# Page_4_Power_CPU_DDR.net
KiCad netlist of a schematic drawn in Altium Designer
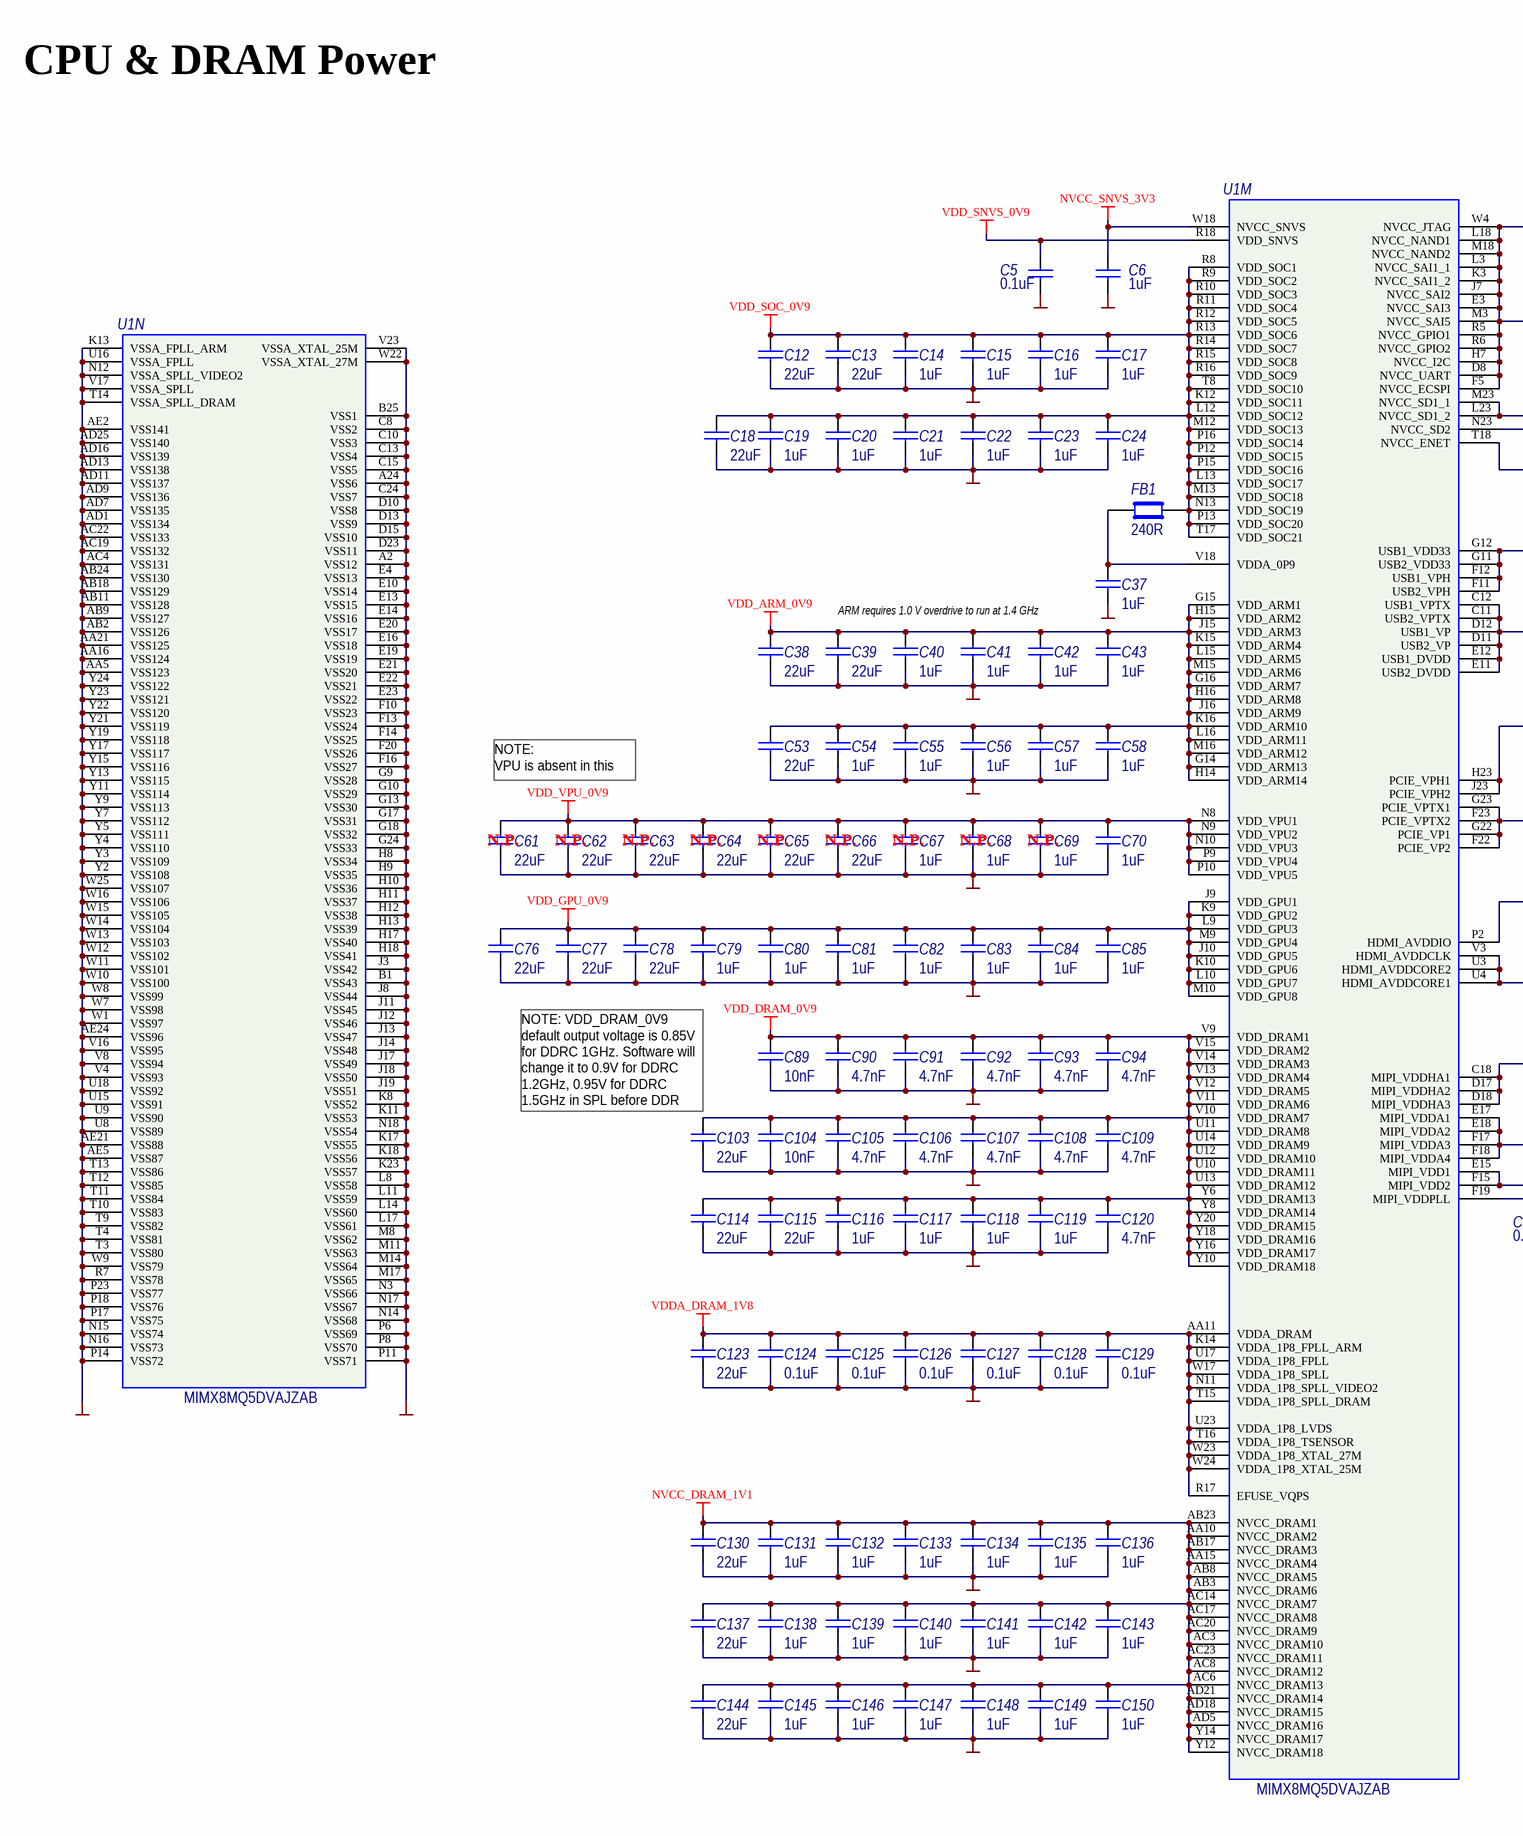
[diagram p0: Page 4_Power CPU_DDR.SchDoc, left]
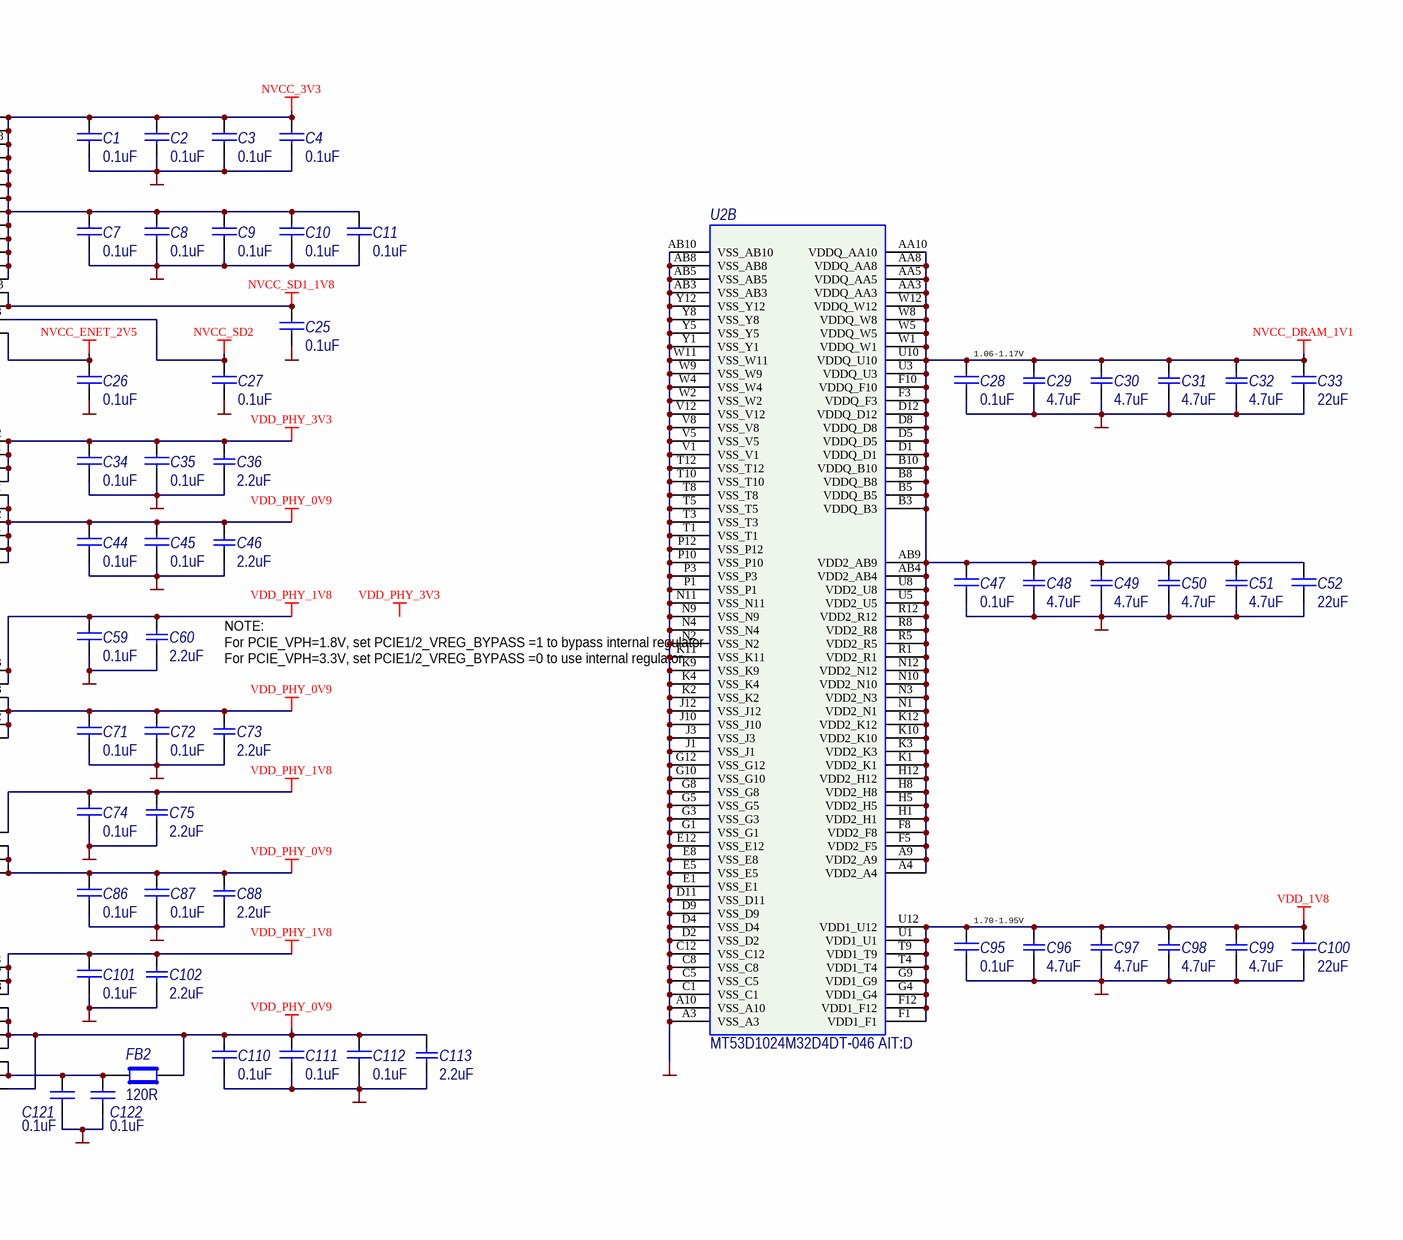
[diagram p1: Page 4_Power CPU_DDR.SchDoc, right]

(export (version "E")
  (design (tool "Eeschema 10.0.6"))
  (components
    (comp (ref "C1")
      (value "0.1uF")
      (footprint "CC0201_L-R")
      (description "CAP CER 0.1 uF 16V 10% X7R 0201")
      (fields
        (field (name "MANUFACTURER") "Murata")
        (field (name "MANUFACTURER PART NUMBER") "GRM033Z71C104KE14D")
      )
      (libsource (lib "CC0201") (part "GRM033Z71C104KE14D"))
    )
    (comp (ref "C2")
      (value "0.1uF")
      (footprint "CC0201_L-R")
      (description "CAP CER 0.1 uF 16V 10% X7R 0201")
      (fields
        (field (name "MANUFACTURER") "Murata")
        (field (name "MANUFACTURER PART NUMBER") "GRM033Z71C104KE14D")
      )
      (libsource (lib "CC0201") (part "GRM033Z71C104KE14D"))
    )
    (comp (ref "C3")
      (value "0.1uF")
      (footprint "CC0201_L-R")
      (description "CAP CER 0.1 uF 16V 10% X7R 0201")
      (fields
        (field (name "MANUFACTURER") "Murata")
        (field (name "MANUFACTURER PART NUMBER") "GRM033Z71C104KE14D")
      )
      (libsource (lib "CC0201") (part "GRM033Z71C104KE14D"))
    )
    (comp (ref "C4")
      (value "0.1uF")
      (footprint "CC0201_L-R")
      (description "CAP CER 0.1 uF 16V 10% X7R 0201")
      (fields
        (field (name "MANUFACTURER") "Murata")
        (field (name "MANUFACTURER PART NUMBER") "GRM033Z71C104KE14D")
      )
      (libsource (lib "CC0201") (part "GRM033Z71C104KE14D"))
    )
    (comp (ref "C5")
      (value "0.1uF")
      (footprint "CC0201_L-R")
      (description "CAP CER 0.1 uF 16V 10% X7R 0201")
      (fields
        (field (name "MANUFACTURER") "Murata")
        (field (name "MANUFACTURER PART NUMBER") "GRM033Z71C104KE14D")
      )
      (libsource (lib "CC0201") (part "GRM033Z71C104KE14D"))
    )
    (comp (ref "C6")
      (value "1uF")
      (footprint "CC0201_L-R")
      (description "CAP CER 1.0 uF 6.3V 10% X5R 0201")
      (fields
        (field (name "MANUFACTURER") "Yageo")
        (field (name "MANUFACTURER PART NUMBER") "CC0201KRX5R5BB105")
      )
      (libsource (lib "CC0201") (part "CC0201KRX5R5BB105"))
    )
    (comp (ref "C7")
      (value "0.1uF")
      (footprint "CC0201_L-R")
      (description "CAP CER 0.1 uF 16V 10% X7R 0201")
      (fields
        (field (name "MANUFACTURER") "Murata")
        (field (name "MANUFACTURER PART NUMBER") "GRM033Z71C104KE14D")
      )
      (libsource (lib "CC0201") (part "GRM033Z71C104KE14D"))
    )
    (comp (ref "C8")
      (value "0.1uF")
      (footprint "CC0201_L-R")
      (description "CAP CER 0.1 uF 16V 10% X7R 0201")
      (fields
        (field (name "MANUFACTURER") "Murata")
        (field (name "MANUFACTURER PART NUMBER") "GRM033Z71C104KE14D")
      )
      (libsource (lib "CC0201") (part "GRM033Z71C104KE14D"))
    )
    (comp (ref "C9")
      (value "0.1uF")
      (footprint "CC0201_L-R")
      (description "CAP CER 0.1 uF 16V 10% X7R 0201")
      (fields
        (field (name "MANUFACTURER") "Murata")
        (field (name "MANUFACTURER PART NUMBER") "GRM033Z71C104KE14D")
      )
      (libsource (lib "CC0201") (part "GRM033Z71C104KE14D"))
    )
    (comp (ref "C10")
      (value "0.1uF")
      (footprint "CC0201_L-R")
      (description "CAP CER 0.1 uF 16V 10% X7R 0201")
      (fields
        (field (name "MANUFACTURER") "Murata")
        (field (name "MANUFACTURER PART NUMBER") "GRM033Z71C104KE14D")
      )
      (libsource (lib "CC0201") (part "GRM033Z71C104KE14D"))
    )
    (comp (ref "C11")
      (value "0.1uF")
      (footprint "CC0201_L-R")
      (description "CAP CER 0.1 uF 16V 10% X7R 0201")
      (fields
        (field (name "MANUFACTURER") "Murata")
        (field (name "MANUFACTURER PART NUMBER") "GRM033Z71C104KE14D")
      )
      (libsource (lib "CC0201") (part "GRM033Z71C104KE14D"))
    )
    (comp (ref "C12")
      (value "22uF")
      (footprint "CC0603_H0.8_L-R")
      (description "CAP CER 22 uF 10V 20% X5R 0603")
      (fields
        (field (name "MANUFACTURER") "Murata")
        (field (name "MANUFACTURER PART NUMBER") "GRM188R61A226ME15J")
      )
      (libsource (lib "CC0603") (part "GRM188R61A226ME15J"))
    )
    (comp (ref "C13")
      (value "22uF")
      (footprint "CC0603_H0.8_L-R")
      (description "CAP CER 22 uF 10V 20% X5R 0603")
      (fields
        (field (name "MANUFACTURER") "Murata")
        (field (name "MANUFACTURER PART NUMBER") "GRM188R61A226ME15J")
      )
      (libsource (lib "CC0603") (part "GRM188R61A226ME15J"))
    )
    (comp (ref "C14")
      (value "1uF")
      (footprint "CC0201_L-R")
      (description "CAP CER 1.0 uF 6.3V 10% X5R 0201")
      (fields
        (field (name "MANUFACTURER") "Yageo")
        (field (name "MANUFACTURER PART NUMBER") "CC0201KRX5R5BB105")
      )
      (libsource (lib "CC0201") (part "CC0201KRX5R5BB105"))
    )
    (comp (ref "C15")
      (value "1uF")
      (footprint "CC0201_L-R")
      (description "CAP CER 1.0 uF 6.3V 10% X5R 0201")
      (fields
        (field (name "MANUFACTURER") "Yageo")
        (field (name "MANUFACTURER PART NUMBER") "CC0201KRX5R5BB105")
      )
      (libsource (lib "CC0201") (part "CC0201KRX5R5BB105"))
    )
    (comp (ref "C16")
      (value "1uF")
      (footprint "CC0201_L-R")
      (description "CAP CER 1.0 uF 6.3V 10% X5R 0201")
      (fields
        (field (name "MANUFACTURER") "Yageo")
        (field (name "MANUFACTURER PART NUMBER") "CC0201KRX5R5BB105")
      )
      (libsource (lib "CC0201") (part "CC0201KRX5R5BB105"))
    )
    (comp (ref "C17")
      (value "1uF")
      (footprint "CC0201_L-R")
      (description "CAP CER 1.0 uF 6.3V 10% X5R 0201")
      (fields
        (field (name "MANUFACTURER") "Yageo")
        (field (name "MANUFACTURER PART NUMBER") "CC0201KRX5R5BB105")
      )
      (libsource (lib "CC0201") (part "CC0201KRX5R5BB105"))
    )
    (comp (ref "C18")
      (value "22uF")
      (footprint "CC0603_H0.8_L-R")
      (description "CAP CER 22 uF 10V 20% X5R 0603")
      (fields
        (field (name "MANUFACTURER") "Murata")
        (field (name "MANUFACTURER PART NUMBER") "GRM188R61A226ME15J")
      )
      (libsource (lib "CC0603") (part "GRM188R61A226ME15J"))
    )
    (comp (ref "C19")
      (value "1uF")
      (footprint "CC0201_L-R")
      (description "CAP CER 1.0 uF 6.3V 10% X5R 0201")
      (fields
        (field (name "MANUFACTURER") "Yageo")
        (field (name "MANUFACTURER PART NUMBER") "CC0201KRX5R5BB105")
      )
      (libsource (lib "CC0201") (part "CC0201KRX5R5BB105"))
    )
    (comp (ref "C20")
      (value "1uF")
      (footprint "CC0201_L-R")
      (description "CAP CER 1.0 uF 6.3V 10% X5R 0201")
      (fields
        (field (name "MANUFACTURER") "Yageo")
        (field (name "MANUFACTURER PART NUMBER") "CC0201KRX5R5BB105")
      )
      (libsource (lib "CC0201") (part "CC0201KRX5R5BB105"))
    )
    (comp (ref "C21")
      (value "1uF")
      (footprint "CC0201_L-R")
      (description "CAP CER 1.0 uF 6.3V 10% X5R 0201")
      (fields
        (field (name "MANUFACTURER") "Yageo")
        (field (name "MANUFACTURER PART NUMBER") "CC0201KRX5R5BB105")
      )
      (libsource (lib "CC0201") (part "CC0201KRX5R5BB105"))
    )
    (comp (ref "C22")
      (value "1uF")
      (footprint "CC0201_L-R")
      (description "CAP CER 1.0 uF 6.3V 10% X5R 0201")
      (fields
        (field (name "MANUFACTURER") "Yageo")
        (field (name "MANUFACTURER PART NUMBER") "CC0201KRX5R5BB105")
      )
      (libsource (lib "CC0201") (part "CC0201KRX5R5BB105"))
    )
    (comp (ref "C23")
      (value "1uF")
      (footprint "CC0201_L-R")
      (description "CAP CER 1.0 uF 6.3V 10% X5R 0201")
      (fields
        (field (name "MANUFACTURER") "Yageo")
        (field (name "MANUFACTURER PART NUMBER") "CC0201KRX5R5BB105")
      )
      (libsource (lib "CC0201") (part "CC0201KRX5R5BB105"))
    )
    (comp (ref "C24")
      (value "1uF")
      (footprint "CC0201_L-R")
      (description "CAP CER 1.0 uF 6.3V 10% X5R 0201")
      (fields
        (field (name "MANUFACTURER") "Yageo")
        (field (name "MANUFACTURER PART NUMBER") "CC0201KRX5R5BB105")
      )
      (libsource (lib "CC0201") (part "CC0201KRX5R5BB105"))
    )
    (comp (ref "C25")
      (value "0.1uF")
      (footprint "CC0201_L-R")
      (description "CAP CER 0.1 uF 16V 10% X7R 0201")
      (fields
        (field (name "MANUFACTURER") "Murata")
        (field (name "MANUFACTURER PART NUMBER") "GRM033Z71C104KE14D")
      )
      (libsource (lib "CC0201") (part "GRM033Z71C104KE14D"))
    )
    (comp (ref "C26")
      (value "0.1uF")
      (footprint "CC0201_L-R")
      (description "CAP CER 0.1 uF 16V 10% X7R 0201")
      (fields
        (field (name "MANUFACTURER") "Murata")
        (field (name "MANUFACTURER PART NUMBER") "GRM033Z71C104KE14D")
      )
      (libsource (lib "CC0201") (part "GRM033Z71C104KE14D"))
    )
    (comp (ref "C27")
      (value "0.1uF")
      (footprint "CC0201_L-R")
      (description "CAP CER 0.1 uF 16V 10% X7R 0201")
      (fields
        (field (name "MANUFACTURER") "Murata")
        (field (name "MANUFACTURER PART NUMBER") "GRM033Z71C104KE14D")
      )
      (libsource (lib "CC0201") (part "GRM033Z71C104KE14D"))
    )
    (comp (ref "C28")
      (value "0.1uF")
      (footprint "CC0201_L-R")
      (description "CAP CER 0.1 uF 16V 10% X7R 0201")
      (fields
        (field (name "MANUFACTURER") "Murata")
        (field (name "MANUFACTURER PART NUMBER") "GRM033Z71C104KE14D")
      )
      (libsource (lib "CC0201") (part "GRM033Z71C104KE14D"))
    )
    (comp (ref "C29")
      (value "4.7uF")
      (footprint "CC0402_L-R")
      (description "CAP CER 4.7uF 10V X5R 10% 0402 Murata")
      (fields
        (field (name "MANUFACTURER") "Murata")
        (field (name "MANUFACTURER PART NUMBER") "GRM155R61A475KEAAD")
      )
      (libsource (lib "CC0402") (part "GRM155R61A475KEAAD"))
    )
    (comp (ref "C30")
      (value "4.7uF")
      (footprint "CC0402_L-R")
      (description "CAP CER 4.7uF 10V X5R 10% 0402 Murata")
      (fields
        (field (name "MANUFACTURER") "Murata")
        (field (name "MANUFACTURER PART NUMBER") "GRM155R61A475KEAAD")
      )
      (libsource (lib "CC0402") (part "GRM155R61A475KEAAD"))
    )
    (comp (ref "C31")
      (value "4.7uF")
      (footprint "CC0402_L-R")
      (description "CAP CER 4.7uF 10V X5R 10% 0402 Murata")
      (fields
        (field (name "MANUFACTURER") "Murata")
        (field (name "MANUFACTURER PART NUMBER") "GRM155R61A475KEAAD")
      )
      (libsource (lib "CC0402") (part "GRM155R61A475KEAAD"))
    )
    (comp (ref "C32")
      (value "4.7uF")
      (footprint "CC0402_L-R")
      (description "CAP CER 4.7uF 10V X5R 10% 0402 Murata")
      (fields
        (field (name "MANUFACTURER") "Murata")
        (field (name "MANUFACTURER PART NUMBER") "GRM155R61A475KEAAD")
      )
      (libsource (lib "CC0402") (part "GRM155R61A475KEAAD"))
    )
    (comp (ref "C33")
      (value "22uF")
      (footprint "CC0603_H0.8_L-R")
      (description "CAP CER 22 uF 10V 20% X5R 0603")
      (fields
        (field (name "MANUFACTURER") "Murata")
        (field (name "MANUFACTURER PART NUMBER") "GRM188R61A226ME15J")
      )
      (libsource (lib "CC0603") (part "GRM188R61A226ME15J"))
    )
    (comp (ref "C34")
      (value "0.1uF")
      (footprint "CC0201_L-R")
      (description "CAP CER 0.1 uF 16V 10% X7R 0201")
      (fields
        (field (name "MANUFACTURER") "Murata")
        (field (name "MANUFACTURER PART NUMBER") "GRM033Z71C104KE14D")
      )
      (libsource (lib "CC0201") (part "GRM033Z71C104KE14D"))
    )
    (comp (ref "C35")
      (value "0.1uF")
      (footprint "CC0201_L-R")
      (description "CAP CER 0.1 uF 16V 10% X7R 0201")
      (fields
        (field (name "MANUFACTURER") "Murata")
        (field (name "MANUFACTURER PART NUMBER") "GRM033Z71C104KE14D")
      )
      (libsource (lib "CC0201") (part "GRM033Z71C104KE14D"))
    )
    (comp (ref "C36")
      (value "2.2uF")
      (footprint "CC0402_L-R")
      (description "CAP CER 2.2 uF 16V X5R 10% 0402 Murata")
      (fields
        (field (name "MANUFACTURER") "Murata")
        (field (name "MANUFACTURER PART NUMBER") "GRT155R61C225KE13D")
      )
      (libsource (lib "CC0402") (part "GRT155R61C225KE13D"))
    )
    (comp (ref "C37")
      (value "1uF")
      (footprint "CC0201_L-R")
      (description "CAP CER 1.0 uF 6.3V 10% X5R 0201")
      (fields
        (field (name "MANUFACTURER") "Yageo")
        (field (name "MANUFACTURER PART NUMBER") "CC0201KRX5R5BB105")
      )
      (libsource (lib "CC0201") (part "CC0201KRX5R5BB105"))
    )
    (comp (ref "C38")
      (value "22uF")
      (footprint "CC0603_H0.8_L-R")
      (description "CAP CER 22 uF 10V 20% X5R 0603")
      (fields
        (field (name "MANUFACTURER") "Murata")
        (field (name "MANUFACTURER PART NUMBER") "GRM188R61A226ME15J")
      )
      (libsource (lib "CC0603") (part "GRM188R61A226ME15J"))
    )
    (comp (ref "C39")
      (value "22uF")
      (footprint "CC0603_H0.8_L-R")
      (description "CAP CER 22 uF 10V 20% X5R 0603")
      (fields
        (field (name "MANUFACTURER") "Murata")
        (field (name "MANUFACTURER PART NUMBER") "GRM188R61A226ME15J")
      )
      (libsource (lib "CC0603") (part "GRM188R61A226ME15J"))
    )
    (comp (ref "C40")
      (value "1uF")
      (footprint "CC0201_L-R")
      (description "CAP CER 1.0 uF 6.3V 10% X5R 0201")
      (fields
        (field (name "MANUFACTURER") "Yageo")
        (field (name "MANUFACTURER PART NUMBER") "CC0201KRX5R5BB105")
      )
      (libsource (lib "CC0201") (part "CC0201KRX5R5BB105"))
    )
    (comp (ref "C41")
      (value "1uF")
      (footprint "CC0201_L-R")
      (description "CAP CER 1.0 uF 6.3V 10% X5R 0201")
      (fields
        (field (name "MANUFACTURER") "Yageo")
        (field (name "MANUFACTURER PART NUMBER") "CC0201KRX5R5BB105")
      )
      (libsource (lib "CC0201") (part "CC0201KRX5R5BB105"))
    )
    (comp (ref "C42")
      (value "1uF")
      (footprint "CC0201_L-R")
      (description "CAP CER 1.0 uF 6.3V 10% X5R 0201")
      (fields
        (field (name "MANUFACTURER") "Yageo")
        (field (name "MANUFACTURER PART NUMBER") "CC0201KRX5R5BB105")
      )
      (libsource (lib "CC0201") (part "CC0201KRX5R5BB105"))
    )
    (comp (ref "C43")
      (value "1uF")
      (footprint "CC0201_L-R")
      (description "CAP CER 1.0 uF 6.3V 10% X5R 0201")
      (fields
        (field (name "MANUFACTURER") "Yageo")
        (field (name "MANUFACTURER PART NUMBER") "CC0201KRX5R5BB105")
      )
      (libsource (lib "CC0201") (part "CC0201KRX5R5BB105"))
    )
    (comp (ref "C44")
      (value "0.1uF")
      (footprint "CC0201_L-R")
      (description "CAP CER 0.1 uF 16V 10% X7R 0201")
      (fields
        (field (name "MANUFACTURER") "Murata")
        (field (name "MANUFACTURER PART NUMBER") "GRM033Z71C104KE14D")
      )
      (libsource (lib "CC0201") (part "GRM033Z71C104KE14D"))
    )
    (comp (ref "C45")
      (value "0.1uF")
      (footprint "CC0201_L-R")
      (description "CAP CER 0.1 uF 16V 10% X7R 0201")
      (fields
        (field (name "MANUFACTURER") "Murata")
        (field (name "MANUFACTURER PART NUMBER") "GRM033Z71C104KE14D")
      )
      (libsource (lib "CC0201") (part "GRM033Z71C104KE14D"))
    )
    (comp (ref "C46")
      (value "2.2uF")
      (footprint "CC0402_L-R")
      (description "CAP CER 2.2 uF 16V X5R 10% 0402 Murata")
      (fields
        (field (name "MANUFACTURER") "Murata")
        (field (name "MANUFACTURER PART NUMBER") "GRT155R61C225KE13D")
      )
      (libsource (lib "CC0402") (part "GRT155R61C225KE13D"))
    )
    (comp (ref "C47")
      (value "0.1uF")
      (footprint "CC0201_L-R")
      (description "CAP CER 0.1 uF 16V 10% X7R 0201")
      (fields
        (field (name "MANUFACTURER") "Murata")
        (field (name "MANUFACTURER PART NUMBER") "GRM033Z71C104KE14D")
      )
      (libsource (lib "CC0201") (part "GRM033Z71C104KE14D"))
    )
    (comp (ref "C48")
      (value "4.7uF")
      (footprint "CC0402_L-R")
      (description "CAP CER 4.7uF 10V X5R 10% 0402 Murata")
      (fields
        (field (name "MANUFACTURER") "Murata")
        (field (name "MANUFACTURER PART NUMBER") "GRM155R61A475KEAAD")
      )
      (libsource (lib "CC0402") (part "GRM155R61A475KEAAD"))
    )
    (comp (ref "C49")
      (value "4.7uF")
      (footprint "CC0402_L-R")
      (description "CAP CER 4.7uF 10V X5R 10% 0402 Murata")
      (fields
        (field (name "MANUFACTURER") "Murata")
        (field (name "MANUFACTURER PART NUMBER") "GRM155R61A475KEAAD")
      )
      (libsource (lib "CC0402") (part "GRM155R61A475KEAAD"))
    )
    (comp (ref "C50")
      (value "4.7uF")
      (footprint "CC0402_L-R")
      (description "CAP CER 4.7uF 10V X5R 10% 0402 Murata")
      (fields
        (field (name "MANUFACTURER") "Murata")
        (field (name "MANUFACTURER PART NUMBER") "GRM155R61A475KEAAD")
      )
      (libsource (lib "CC0402") (part "GRM155R61A475KEAAD"))
    )
    (comp (ref "C51")
      (value "4.7uF")
      (footprint "CC0402_L-R")
      (description "CAP CER 4.7uF 10V X5R 10% 0402 Murata")
      (fields
        (field (name "MANUFACTURER") "Murata")
        (field (name "MANUFACTURER PART NUMBER") "GRM155R61A475KEAAD")
      )
      (libsource (lib "CC0402") (part "GRM155R61A475KEAAD"))
    )
    (comp (ref "C52")
      (value "22uF")
      (footprint "CC0603_H0.8_L-R")
      (description "CAP CER 22 uF 10V 20% X5R 0603")
      (fields
        (field (name "MANUFACTURER") "Murata")
        (field (name "MANUFACTURER PART NUMBER") "GRM188R61A226ME15J")
      )
      (libsource (lib "CC0603") (part "GRM188R61A226ME15J"))
    )
    (comp (ref "C53")
      (value "22uF")
      (footprint "CC0603_H0.8_L-R")
      (description "CAP CER 22 uF 10V 20% X5R 0603")
      (fields
        (field (name "MANUFACTURER") "Murata")
        (field (name "MANUFACTURER PART NUMBER") "GRM188R61A226ME15J")
      )
      (libsource (lib "CC0603") (part "GRM188R61A226ME15J"))
    )
    (comp (ref "C54")
      (value "1uF")
      (footprint "CC0201_L-R")
      (description "CAP CER 1.0 uF 6.3V 10% X5R 0201")
      (fields
        (field (name "MANUFACTURER") "Yageo")
        (field (name "MANUFACTURER PART NUMBER") "CC0201KRX5R5BB105")
      )
      (libsource (lib "CC0201") (part "CC0201KRX5R5BB105"))
    )
    (comp (ref "C55")
      (value "1uF")
      (footprint "CC0201_L-R")
      (description "CAP CER 1.0 uF 6.3V 10% X5R 0201")
      (fields
        (field (name "MANUFACTURER") "Yageo")
        (field (name "MANUFACTURER PART NUMBER") "CC0201KRX5R5BB105")
      )
      (libsource (lib "CC0201") (part "CC0201KRX5R5BB105"))
    )
    (comp (ref "C56")
      (value "1uF")
      (footprint "CC0201_L-R")
      (description "CAP CER 1.0 uF 6.3V 10% X5R 0201")
      (fields
        (field (name "MANUFACTURER") "Yageo")
        (field (name "MANUFACTURER PART NUMBER") "CC0201KRX5R5BB105")
      )
      (libsource (lib "CC0201") (part "CC0201KRX5R5BB105"))
    )
    (comp (ref "C57")
      (value "1uF")
      (footprint "CC0201_L-R")
      (description "CAP CER 1.0 uF 6.3V 10% X5R 0201")
      (fields
        (field (name "MANUFACTURER") "Yageo")
        (field (name "MANUFACTURER PART NUMBER") "CC0201KRX5R5BB105")
      )
      (libsource (lib "CC0201") (part "CC0201KRX5R5BB105"))
    )
    (comp (ref "C58")
      (value "1uF")
      (footprint "CC0201_L-R")
      (description "CAP CER 1.0 uF 6.3V 10% X5R 0201")
      (fields
        (field (name "MANUFACTURER") "Yageo")
        (field (name "MANUFACTURER PART NUMBER") "CC0201KRX5R5BB105")
      )
      (libsource (lib "CC0201") (part "CC0201KRX5R5BB105"))
    )
    (comp (ref "C59")
      (value "0.1uF")
      (footprint "CC0201_L-R")
      (description "CAP CER 0.1 uF 16V 10% X7R 0201")
      (fields
        (field (name "MANUFACTURER") "Murata")
        (field (name "MANUFACTURER PART NUMBER") "GRM033Z71C104KE14D")
      )
      (libsource (lib "CC0201") (part "GRM033Z71C104KE14D"))
    )
    (comp (ref "C60")
      (value "2.2uF")
      (footprint "CC0402_L-R")
      (description "CAP CER 2.2 uF 16V X5R 10% 0402 Murata")
      (fields
        (field (name "MANUFACTURER") "Murata")
        (field (name "MANUFACTURER PART NUMBER") "GRT155R61C225KE13D")
      )
      (libsource (lib "CC0402") (part "GRT155R61C225KE13D"))
    )
    (comp (ref "C61")
      (value "22uF")
      (footprint "CC0603_H0.8_L-R")
      (description "CAP CER 22 uF 10V 20% X5R 0603")
      (fields
        (field (name "MANUFACTURER") "Murata")
        (field (name "MANUFACTURER PART NUMBER") "GRM188R61A226ME15J")
      )
      (libsource (lib "CC0603") (part "GRM188R61A226ME15J"))
    )
    (comp (ref "C62")
      (value "22uF")
      (footprint "CC0603_H0.8_L-R")
      (description "CAP CER 22 uF 10V 20% X5R 0603")
      (fields
        (field (name "MANUFACTURER") "Murata")
        (field (name "MANUFACTURER PART NUMBER") "GRM188R61A226ME15J")
      )
      (libsource (lib "CC0603") (part "GRM188R61A226ME15J"))
    )
    (comp (ref "C63")
      (value "22uF")
      (footprint "CC0603_H0.8_L-R")
      (description "CAP CER 22 uF 10V 20% X5R 0603")
      (fields
        (field (name "MANUFACTURER") "Murata")
        (field (name "MANUFACTURER PART NUMBER") "GRM188R61A226ME15J")
      )
      (libsource (lib "CC0603") (part "GRM188R61A226ME15J"))
    )
    (comp (ref "C64")
      (value "22uF")
      (footprint "CC0603_H0.8_L-R")
      (description "CAP CER 22 uF 10V 20% X5R 0603")
      (fields
        (field (name "MANUFACTURER") "Murata")
        (field (name "MANUFACTURER PART NUMBER") "GRM188R61A226ME15J")
      )
      (libsource (lib "CC0603") (part "GRM188R61A226ME15J"))
    )
    (comp (ref "C65")
      (value "22uF")
      (footprint "CC0603_H0.8_L-R")
      (description "CAP CER 22 uF 10V 20% X5R 0603")
      (fields
        (field (name "MANUFACTURER") "Murata")
        (field (name "MANUFACTURER PART NUMBER") "GRM188R61A226ME15J")
      )
      (libsource (lib "CC0603") (part "GRM188R61A226ME15J"))
    )
    (comp (ref "C66")
      (value "22uF")
      (footprint "CC0603_H0.8_L-R")
      (description "CAP CER 22 uF 10V 20% X5R 0603")
      (fields
        (field (name "MANUFACTURER") "Murata")
        (field (name "MANUFACTURER PART NUMBER") "GRM188R61A226ME15J")
      )
      (libsource (lib "CC0603") (part "GRM188R61A226ME15J"))
    )
    (comp (ref "C67")
      (value "1uF")
      (footprint "CC0201_L-R")
      (description "CAP CER 1.0 uF 6.3V 10% X5R 0201")
      (fields
        (field (name "MANUFACTURER") "Yageo")
        (field (name "MANUFACTURER PART NUMBER") "CC0201KRX5R5BB105")
      )
      (libsource (lib "CC0201") (part "CC0201KRX5R5BB105"))
    )
    (comp (ref "C68")
      (value "1uF")
      (footprint "CC0201_L-R")
      (description "CAP CER 1.0 uF 6.3V 10% X5R 0201")
      (fields
        (field (name "MANUFACTURER") "Yageo")
        (field (name "MANUFACTURER PART NUMBER") "CC0201KRX5R5BB105")
      )
      (libsource (lib "CC0201") (part "CC0201KRX5R5BB105"))
    )
    (comp (ref "C69")
      (value "1uF")
      (footprint "CC0201_L-R")
      (description "CAP CER 1.0 uF 6.3V 10% X5R 0201")
      (fields
        (field (name "MANUFACTURER") "Yageo")
        (field (name "MANUFACTURER PART NUMBER") "CC0201KRX5R5BB105")
      )
      (libsource (lib "CC0201") (part "CC0201KRX5R5BB105"))
    )
    (comp (ref "C70")
      (value "1uF")
      (footprint "CC0201_L-R")
      (description "CAP CER 1.0 uF 6.3V 10% X5R 0201")
      (fields
        (field (name "MANUFACTURER") "Yageo")
        (field (name "MANUFACTURER PART NUMBER") "CC0201KRX5R5BB105")
      )
      (libsource (lib "CC0201") (part "CC0201KRX5R5BB105"))
    )
    (comp (ref "C71")
      (value "0.1uF")
      (footprint "CC0201_L-R")
      (description "CAP CER 0.1 uF 16V 10% X7R 0201")
      (fields
        (field (name "MANUFACTURER") "Murata")
        (field (name "MANUFACTURER PART NUMBER") "GRM033Z71C104KE14D")
      )
      (libsource (lib "CC0201") (part "GRM033Z71C104KE14D"))
    )
    (comp (ref "C72")
      (value "0.1uF")
      (footprint "CC0201_L-R")
      (description "CAP CER 0.1 uF 16V 10% X7R 0201")
      (fields
        (field (name "MANUFACTURER") "Murata")
        (field (name "MANUFACTURER PART NUMBER") "GRM033Z71C104KE14D")
      )
      (libsource (lib "CC0201") (part "GRM033Z71C104KE14D"))
    )
    (comp (ref "C73")
      (value "2.2uF")
      (footprint "CC0402_L-R")
      (description "CAP CER 2.2 uF 16V X5R 10% 0402 Murata")
      (fields
        (field (name "MANUFACTURER") "Murata")
        (field (name "MANUFACTURER PART NUMBER") "GRT155R61C225KE13D")
      )
      (libsource (lib "CC0402") (part "GRT155R61C225KE13D"))
    )
    (comp (ref "C74")
      (value "0.1uF")
      (footprint "CC0201_L-R")
      (description "CAP CER 0.1 uF 16V 10% X7R 0201")
      (fields
        (field (name "MANUFACTURER") "Murata")
        (field (name "MANUFACTURER PART NUMBER") "GRM033Z71C104KE14D")
      )
      (libsource (lib "CC0201") (part "GRM033Z71C104KE14D"))
    )
    (comp (ref "C75")
      (value "2.2uF")
      (footprint "CC0402_L-R")
      (description "CAP CER 2.2 uF 16V X5R 10% 0402 Murata")
      (fields
        (field (name "MANUFACTURER") "Murata")
        (field (name "MANUFACTURER PART NUMBER") "GRT155R61C225KE13D")
      )
      (libsource (lib "CC0402") (part "GRT155R61C225KE13D"))
    )
    (comp (ref "C76")
      (value "22uF")
      (footprint "CC0603_H0.8_L-R")
      (description "CAP CER 22 uF 10V 20% X5R 0603")
      (fields
        (field (name "MANUFACTURER") "Murata")
        (field (name "MANUFACTURER PART NUMBER") "GRM188R61A226ME15J")
      )
      (libsource (lib "CC0603") (part "GRM188R61A226ME15J"))
    )
    (comp (ref "C77")
      (value "22uF")
      (footprint "CC0603_H0.8_L-R")
      (description "CAP CER 22 uF 10V 20% X5R 0603")
      (fields
        (field (name "MANUFACTURER") "Murata")
        (field (name "MANUFACTURER PART NUMBER") "GRM188R61A226ME15J")
      )
      (libsource (lib "CC0603") (part "GRM188R61A226ME15J"))
    )
    (comp (ref "C78")
      (value "22uF")
      (footprint "CC0603_H0.8_L-R")
      (description "CAP CER 22 uF 10V 20% X5R 0603")
      (fields
        (field (name "MANUFACTURER") "Murata")
        (field (name "MANUFACTURER PART NUMBER") "GRM188R61A226ME15J")
      )
      (libsource (lib "CC0603") (part "GRM188R61A226ME15J"))
    )
    (comp (ref "C79")
      (value "1uF")
      (footprint "CC0201_L-R")
      (description "CAP CER 1.0 uF 6.3V 10% X5R 0201")
      (fields
        (field (name "MANUFACTURER") "Yageo")
        (field (name "MANUFACTURER PART NUMBER") "CC0201KRX5R5BB105")
      )
      (libsource (lib "CC0201") (part "CC0201KRX5R5BB105"))
    )
    (comp (ref "C80")
      (value "1uF")
      (footprint "CC0201_L-R")
      (description "CAP CER 1.0 uF 6.3V 10% X5R 0201")
      (fields
        (field (name "MANUFACTURER") "Yageo")
        (field (name "MANUFACTURER PART NUMBER") "CC0201KRX5R5BB105")
      )
      (libsource (lib "CC0201") (part "CC0201KRX5R5BB105"))
    )
    (comp (ref "C81")
      (value "1uF")
      (footprint "CC0201_L-R")
      (description "CAP CER 1.0 uF 6.3V 10% X5R 0201")
      (fields
        (field (name "MANUFACTURER") "Yageo")
        (field (name "MANUFACTURER PART NUMBER") "CC0201KRX5R5BB105")
      )
      (libsource (lib "CC0201") (part "CC0201KRX5R5BB105"))
    )
    (comp (ref "C82")
      (value "1uF")
      (footprint "CC0201_L-R")
      (description "CAP CER 1.0 uF 6.3V 10% X5R 0201")
      (fields
        (field (name "MANUFACTURER") "Yageo")
        (field (name "MANUFACTURER PART NUMBER") "CC0201KRX5R5BB105")
      )
      (libsource (lib "CC0201") (part "CC0201KRX5R5BB105"))
    )
    (comp (ref "C83")
      (value "1uF")
      (footprint "CC0201_L-R")
      (description "CAP CER 1.0 uF 6.3V 10% X5R 0201")
      (fields
        (field (name "MANUFACTURER") "Yageo")
        (field (name "MANUFACTURER PART NUMBER") "CC0201KRX5R5BB105")
      )
      (libsource (lib "CC0201") (part "CC0201KRX5R5BB105"))
    )
    (comp (ref "C84")
      (value "1uF")
      (footprint "CC0201_L-R")
      (description "CAP CER 1.0 uF 6.3V 10% X5R 0201")
      (fields
        (field (name "MANUFACTURER") "Yageo")
        (field (name "MANUFACTURER PART NUMBER") "CC0201KRX5R5BB105")
      )
      (libsource (lib "CC0201") (part "CC0201KRX5R5BB105"))
    )
    (comp (ref "C85")
      (value "1uF")
      (footprint "CC0201_L-R")
      (description "CAP CER 1.0 uF 6.3V 10% X5R 0201")
      (fields
        (field (name "MANUFACTURER") "Yageo")
        (field (name "MANUFACTURER PART NUMBER") "CC0201KRX5R5BB105")
      )
      (libsource (lib "CC0201") (part "CC0201KRX5R5BB105"))
    )
    (comp (ref "C86")
      (value "0.1uF")
      (footprint "CC0201_L-R")
      (description "CAP CER 0.1 uF 16V 10% X7R 0201")
      (fields
        (field (name "MANUFACTURER") "Murata")
        (field (name "MANUFACTURER PART NUMBER") "GRM033Z71C104KE14D")
      )
      (libsource (lib "CC0201") (part "GRM033Z71C104KE14D"))
    )
    (comp (ref "C87")
      (value "0.1uF")
      (footprint "CC0201_L-R")
      (description "CAP CER 0.1 uF 16V 10% X7R 0201")
      (fields
        (field (name "MANUFACTURER") "Murata")
        (field (name "MANUFACTURER PART NUMBER") "GRM033Z71C104KE14D")
      )
      (libsource (lib "CC0201") (part "GRM033Z71C104KE14D"))
    )
    (comp (ref "C88")
      (value "2.2uF")
      (footprint "CC0402_L-R")
      (description "CAP CER 2.2 uF 16V X5R 10% 0402 Murata")
      (fields
        (field (name "MANUFACTURER") "Murata")
        (field (name "MANUFACTURER PART NUMBER") "GRT155R61C225KE13D")
      )
      (libsource (lib "CC0402") (part "GRT155R61C225KE13D"))
    )
    (comp (ref "C89")
      (value "10nF")
      (footprint "CC0201_L-R")
      (description "CAP CER 10 nF 16V 10% X7R 0201")
      (fields
        (field (name "MANUFACTURER") "Murata")
        (field (name "MANUFACTURER PART NUMBER") "GRM033R71C103KE14D")
      )
      (libsource (lib "CC0201") (part "GRM033R71C103KE14D"))
    )
    (comp (ref "C90")
      (value "4.7nF")
      (footprint "CC0201_L-R")
      (description "CAP CER 4.7 nF 16V 10% X7R 0201")
      (fields
        (field (name "MANUFACTURER") "Murata")
        (field (name "MANUFACTURER PART NUMBER") "GRM033R71C472KE14D")
      )
      (libsource (lib "CC0201") (part "GRM033R71C472KE14D"))
    )
    (comp (ref "C91")
      (value "4.7nF")
      (footprint "CC0201_L-R")
      (description "CAP CER 4.7 nF 16V 10% X7R 0201")
      (fields
        (field (name "MANUFACTURER") "Murata")
        (field (name "MANUFACTURER PART NUMBER") "GRM033R71C472KE14D")
      )
      (libsource (lib "CC0201") (part "GRM033R71C472KE14D"))
    )
    (comp (ref "C92")
      (value "4.7nF")
      (footprint "CC0201_L-R")
      (description "CAP CER 4.7 nF 16V 10% X7R 0201")
      (fields
        (field (name "MANUFACTURER") "Murata")
        (field (name "MANUFACTURER PART NUMBER") "GRM033R71C472KE14D")
      )
      (libsource (lib "CC0201") (part "GRM033R71C472KE14D"))
    )
    (comp (ref "C93")
      (value "4.7nF")
      (footprint "CC0201_L-R")
      (description "CAP CER 4.7 nF 16V 10% X7R 0201")
      (fields
        (field (name "MANUFACTURER") "Murata")
        (field (name "MANUFACTURER PART NUMBER") "GRM033R71C472KE14D")
      )
      (libsource (lib "CC0201") (part "GRM033R71C472KE14D"))
    )
    (comp (ref "C94")
      (value "4.7nF")
      (footprint "CC0201_L-R")
      (description "CAP CER 4.7 nF 16V 10% X7R 0201")
      (fields
        (field (name "MANUFACTURER") "Murata")
        (field (name "MANUFACTURER PART NUMBER") "GRM033R71C472KE14D")
      )
      (libsource (lib "CC0201") (part "GRM033R71C472KE14D"))
    )
    (comp (ref "C95")
      (value "0.1uF")
      (footprint "CC0201_L-R")
      (description "CAP CER 0.1 uF 16V 10% X7R 0201")
      (fields
        (field (name "MANUFACTURER") "Murata")
        (field (name "MANUFACTURER PART NUMBER") "GRM033Z71C104KE14D")
      )
      (libsource (lib "CC0201") (part "GRM033Z71C104KE14D"))
    )
    (comp (ref "C96")
      (value "4.7uF")
      (footprint "CC0402_L-R")
      (description "CAP CER 4.7uF 10V X5R 10% 0402 Murata")
      (fields
        (field (name "MANUFACTURER") "Murata")
        (field (name "MANUFACTURER PART NUMBER") "GRM155R61A475KEAAD")
      )
      (libsource (lib "CC0402") (part "GRM155R61A475KEAAD"))
    )
    (comp (ref "C97")
      (value "4.7uF")
      (footprint "CC0402_L-R")
      (description "CAP CER 4.7uF 10V X5R 10% 0402 Murata")
      (fields
        (field (name "MANUFACTURER") "Murata")
        (field (name "MANUFACTURER PART NUMBER") "GRM155R61A475KEAAD")
      )
      (libsource (lib "CC0402") (part "GRM155R61A475KEAAD"))
    )
    (comp (ref "C98")
      (value "4.7uF")
      (footprint "CC0402_L-R")
      (description "CAP CER 4.7uF 10V X5R 10% 0402 Murata")
      (fields
        (field (name "MANUFACTURER") "Murata")
        (field (name "MANUFACTURER PART NUMBER") "GRM155R61A475KEAAD")
      )
      (libsource (lib "CC0402") (part "GRM155R61A475KEAAD"))
    )
    (comp (ref "C99")
      (value "4.7uF")
      (footprint "CC0402_L-R")
      (description "CAP CER 4.7uF 10V X5R 10% 0402 Murata")
      (fields
        (field (name "MANUFACTURER") "Murata")
        (field (name "MANUFACTURER PART NUMBER") "GRM155R61A475KEAAD")
      )
      (libsource (lib "CC0402") (part "GRM155R61A475KEAAD"))
    )
    (comp (ref "C100")
      (value "22uF")
      (footprint "CC0603_H0.8_L-R")
      (description "CAP CER 22 uF 10V 20% X5R 0603")
      (fields
        (field (name "MANUFACTURER") "Murata")
        (field (name "MANUFACTURER PART NUMBER") "GRM188R61A226ME15J")
      )
      (libsource (lib "CC0603") (part "GRM188R61A226ME15J"))
    )
    (comp (ref "C101")
      (value "0.1uF")
      (footprint "CC0201_L-R")
      (description "CAP CER 0.1 uF 16V 10% X7R 0201")
      (fields
        (field (name "MANUFACTURER") "Murata")
        (field (name "MANUFACTURER PART NUMBER") "GRM033Z71C104KE14D")
      )
      (libsource (lib "CC0201") (part "GRM033Z71C104KE14D"))
    )
    (comp (ref "C102")
      (value "2.2uF")
      (footprint "CC0402_L-R")
      (description "CAP CER 2.2 uF 16V X5R 10% 0402 Murata")
      (fields
        (field (name "MANUFACTURER") "Murata")
        (field (name "MANUFACTURER PART NUMBER") "GRT155R61C225KE13D")
      )
      (libsource (lib "CC0402") (part "GRT155R61C225KE13D"))
    )
    (comp (ref "C103")
      (value "22uF")
      (footprint "CC0603_H0.8_L-R")
      (description "CAP CER 22 uF 10V 20% X5R 0603")
      (fields
        (field (name "MANUFACTURER") "Murata")
        (field (name "MANUFACTURER PART NUMBER") "GRM188R61A226ME15J")
      )
      (libsource (lib "CC0603") (part "GRM188R61A226ME15J"))
    )
    (comp (ref "C104")
      (value "10nF")
      (footprint "CC0201_L-R")
      (description "CAP CER 10 nF 16V 10% X7R 0201")
      (fields
        (field (name "MANUFACTURER") "Murata")
        (field (name "MANUFACTURER PART NUMBER") "GRM033R71C103KE14D")
      )
      (libsource (lib "CC0201") (part "GRM033R71C103KE14D"))
    )
    (comp (ref "C105")
      (value "4.7nF")
      (footprint "CC0201_L-R")
      (description "CAP CER 4.7 nF 16V 10% X7R 0201")
      (fields
        (field (name "MANUFACTURER") "Murata")
        (field (name "MANUFACTURER PART NUMBER") "GRM033R71C472KE14D")
      )
      (libsource (lib "CC0201") (part "GRM033R71C472KE14D"))
    )
    (comp (ref "C106")
      (value "4.7nF")
      (footprint "CC0201_L-R")
      (description "CAP CER 4.7 nF 16V 10% X7R 0201")
      (fields
        (field (name "MANUFACTURER") "Murata")
        (field (name "MANUFACTURER PART NUMBER") "GRM033R71C472KE14D")
      )
      (libsource (lib "CC0201") (part "GRM033R71C472KE14D"))
    )
    (comp (ref "C107")
      (value "4.7nF")
      (footprint "CC0201_L-R")
      (description "CAP CER 4.7 nF 16V 10% X7R 0201")
      (fields
        (field (name "MANUFACTURER") "Murata")
        (field (name "MANUFACTURER PART NUMBER") "GRM033R71C472KE14D")
      )
      (libsource (lib "CC0201") (part "GRM033R71C472KE14D"))
    )
    (comp (ref "C108")
      (value "4.7nF")
      (footprint "CC0201_L-R")
      (description "CAP CER 4.7 nF 16V 10% X7R 0201")
      (fields
        (field (name "MANUFACTURER") "Murata")
        (field (name "MANUFACTURER PART NUMBER") "GRM033R71C472KE14D")
      )
      (libsource (lib "CC0201") (part "GRM033R71C472KE14D"))
    )
    (comp (ref "C109")
      (value "4.7nF")
      (footprint "CC0201_L-R")
      (description "CAP CER 4.7 nF 16V 10% X7R 0201")
      (fields
        (field (name "MANUFACTURER") "Murata")
        (field (name "MANUFACTURER PART NUMBER") "GRM033R71C472KE14D")
      )
      (libsource (lib "CC0201") (part "GRM033R71C472KE14D"))
    )
    (comp (ref "C110")
      (value "0.1uF")
      (footprint "CC0201_L-R")
      (description "CAP CER 0.1 uF 16V 10% X7R 0201")
      (fields
        (field (name "MANUFACTURER") "Murata")
        (field (name "MANUFACTURER PART NUMBER") "GRM033Z71C104KE14D")
      )
      (libsource (lib "CC0201") (part "GRM033Z71C104KE14D"))
    )
    (comp (ref "C111")
      (value "0.1uF")
      (footprint "CC0201_L-R")
      (description "CAP CER 0.1 uF 16V 10% X7R 0201")
      (fields
        (field (name "MANUFACTURER") "Murata")
        (field (name "MANUFACTURER PART NUMBER") "GRM033Z71C104KE14D")
      )
      (libsource (lib "CC0201") (part "GRM033Z71C104KE14D"))
    )
    (comp (ref "C112")
      (value "0.1uF")
      (footprint "CC0201_L-R")
      (description "CAP CER 0.1 uF 16V 10% X7R 0201")
      (fields
        (field (name "MANUFACTURER") "Murata")
        (field (name "MANUFACTURER PART NUMBER") "GRM033Z71C104KE14D")
      )
      (libsource (lib "CC0201") (part "GRM033Z71C104KE14D"))
    )
    (comp (ref "C113")
      (value "2.2uF")
      (footprint "CC0402_L-R")
      (description "CAP CER 2.2 uF 16V X5R 10% 0402 Murata")
      (fields
        (field (name "MANUFACTURER") "Murata")
        (field (name "MANUFACTURER PART NUMBER") "GRT155R61C225KE13D")
      )
      (libsource (lib "CC0402") (part "GRT155R61C225KE13D"))
    )
    (comp (ref "C114")
      (value "22uF")
      (footprint "CC0603_H0.8_L-R")
      (description "CAP CER 22 uF 10V 20% X5R 0603")
      (fields
        (field (name "MANUFACTURER") "Murata")
        (field (name "MANUFACTURER PART NUMBER") "GRM188R61A226ME15J")
      )
      (libsource (lib "CC0603") (part "GRM188R61A226ME15J"))
    )
    (comp (ref "C115")
      (value "22uF")
      (footprint "CC0603_H0.8_L-R")
      (description "CAP CER 22 uF 10V 20% X5R 0603")
      (fields
        (field (name "MANUFACTURER") "Murata")
        (field (name "MANUFACTURER PART NUMBER") "GRM188R61A226ME15J")
      )
      (libsource (lib "CC0603") (part "GRM188R61A226ME15J"))
    )
    (comp (ref "C116")
      (value "1uF")
      (footprint "CC0201_L-R")
      (description "CAP CER 1.0 uF 6.3V 10% X5R 0201")
      (fields
        (field (name "MANUFACTURER") "Yageo")
        (field (name "MANUFACTURER PART NUMBER") "CC0201KRX5R5BB105")
      )
      (libsource (lib "CC0201") (part "CC0201KRX5R5BB105"))
    )
    (comp (ref "C117")
      (value "1uF")
      (footprint "CC0201_L-R")
      (description "CAP CER 1.0 uF 6.3V 10% X5R 0201")
      (fields
        (field (name "MANUFACTURER") "Yageo")
        (field (name "MANUFACTURER PART NUMBER") "CC0201KRX5R5BB105")
      )
      (libsource (lib "CC0201") (part "CC0201KRX5R5BB105"))
    )
    (comp (ref "C118")
      (value "1uF")
      (footprint "CC0201_L-R")
      (description "CAP CER 1.0 uF 6.3V 10% X5R 0201")
      (fields
        (field (name "MANUFACTURER") "Yageo")
        (field (name "MANUFACTURER PART NUMBER") "CC0201KRX5R5BB105")
      )
      (libsource (lib "CC0201") (part "CC0201KRX5R5BB105"))
    )
    (comp (ref "C119")
      (value "1uF")
      (footprint "CC0201_L-R")
      (description "CAP CER 1.0 uF 6.3V 10% X5R 0201")
      (fields
        (field (name "MANUFACTURER") "Yageo")
        (field (name "MANUFACTURER PART NUMBER") "CC0201KRX5R5BB105")
      )
      (libsource (lib "CC0201") (part "CC0201KRX5R5BB105"))
    )
    (comp (ref "C120")
      (value "4.7nF")
      (footprint "CC0201_L-R")
      (description "CAP CER 4.7 nF 16V 10% X7R 0201")
      (fields
        (field (name "MANUFACTURER") "Murata")
        (field (name "MANUFACTURER PART NUMBER") "GRM033R71C472KE14D")
      )
      (libsource (lib "CC0201") (part "GRM033R71C472KE14D"))
    )
    (comp (ref "C121")
      (value "0.1uF")
      (footprint "CC0201_L-R")
      (description "CAP CER 0.1 uF 16V 10% X7R 0201")
      (fields
        (field (name "MANUFACTURER") "Murata")
        (field (name "MANUFACTURER PART NUMBER") "GRM033Z71C104KE14D")
      )
      (libsource (lib "CC0201") (part "GRM033Z71C104KE14D"))
    )
    (comp (ref "C122")
      (value "0.1uF")
      (footprint "CC0201_L-R")
      (description "CAP CER 0.1 uF 16V 10% X7R 0201")
      (fields
        (field (name "MANUFACTURER") "Murata")
        (field (name "MANUFACTURER PART NUMBER") "GRM033Z71C104KE14D")
      )
      (libsource (lib "CC0201") (part "GRM033Z71C104KE14D"))
    )
    (comp (ref "C123")
      (value "22uF")
      (footprint "CC0603_H0.8_L-R")
      (description "CAP CER 22 uF 10V 20% X5R 0603")
      (fields
        (field (name "MANUFACTURER") "Murata")
        (field (name "MANUFACTURER PART NUMBER") "GRM188R61A226ME15J")
      )
      (libsource (lib "CC0603") (part "GRM188R61A226ME15J"))
    )
    (comp (ref "C124")
      (value "0.1uF")
      (footprint "CC0201_L-R")
      (description "CAP CER 0.1 uF 16V 10% X7R 0201")
      (fields
        (field (name "MANUFACTURER") "Murata")
        (field (name "MANUFACTURER PART NUMBER") "GRM033Z71C104KE14D")
      )
      (libsource (lib "CC0201") (part "GRM033Z71C104KE14D"))
    )
    (comp (ref "C125")
      (value "0.1uF")
      (footprint "CC0201_L-R")
      (description "CAP CER 0.1 uF 16V 10% X7R 0201")
      (fields
        (field (name "MANUFACTURER") "Murata")
        (field (name "MANUFACTURER PART NUMBER") "GRM033Z71C104KE14D")
      )
      (libsource (lib "CC0201") (part "GRM033Z71C104KE14D"))
    )
    (comp (ref "C126")
      (value "0.1uF")
      (footprint "CC0201_L-R")
      (description "CAP CER 0.1 uF 16V 10% X7R 0201")
      (fields
        (field (name "MANUFACTURER") "Murata")
        (field (name "MANUFACTURER PART NUMBER") "GRM033Z71C104KE14D")
      )
      (libsource (lib "CC0201") (part "GRM033Z71C104KE14D"))
    )
    (comp (ref "C127")
      (value "0.1uF")
      (footprint "CC0201_L-R")
      (description "CAP CER 0.1 uF 16V 10% X7R 0201")
      (fields
        (field (name "MANUFACTURER") "Murata")
        (field (name "MANUFACTURER PART NUMBER") "GRM033Z71C104KE14D")
      )
      (libsource (lib "CC0201") (part "GRM033Z71C104KE14D"))
    )
    (comp (ref "C128")
      (value "0.1uF")
      (footprint "CC0201_L-R")
      (description "CAP CER 0.1 uF 16V 10% X7R 0201")
      (fields
        (field (name "MANUFACTURER") "Murata")
        (field (name "MANUFACTURER PART NUMBER") "GRM033Z71C104KE14D")
      )
      (libsource (lib "CC0201") (part "GRM033Z71C104KE14D"))
    )
    (comp (ref "C129")
      (value "0.1uF")
      (footprint "CC0201_L-R")
      (description "CAP CER 0.1 uF 16V 10% X7R 0201")
      (fields
        (field (name "MANUFACTURER") "Murata")
        (field (name "MANUFACTURER PART NUMBER") "GRM033Z71C104KE14D")
      )
      (libsource (lib "CC0201") (part "GRM033Z71C104KE14D"))
    )
    (comp (ref "C130")
      (value "22uF")
      (footprint "CC0603_H0.8_L-R")
      (description "CAP CER 22 uF 10V 20% X5R 0603")
      (fields
        (field (name "MANUFACTURER") "Murata")
        (field (name "MANUFACTURER PART NUMBER") "GRM188R61A226ME15J")
      )
      (libsource (lib "CC0603") (part "GRM188R61A226ME15J"))
    )
    (comp (ref "C131")
      (value "1uF")
      (footprint "CC0201_L-R")
      (description "CAP CER 1.0 uF 6.3V 10% X5R 0201")
      (fields
        (field (name "MANUFACTURER") "Yageo")
        (field (name "MANUFACTURER PART NUMBER") "CC0201KRX5R5BB105")
      )
      (libsource (lib "CC0201") (part "CC0201KRX5R5BB105"))
    )
    (comp (ref "C132")
      (value "1uF")
      (footprint "CC0201_L-R")
      (description "CAP CER 1.0 uF 6.3V 10% X5R 0201")
      (fields
        (field (name "MANUFACTURER") "Yageo")
        (field (name "MANUFACTURER PART NUMBER") "CC0201KRX5R5BB105")
      )
      (libsource (lib "CC0201") (part "CC0201KRX5R5BB105"))
    )
    (comp (ref "C133")
      (value "1uF")
      (footprint "CC0201_L-R")
      (description "CAP CER 1.0 uF 6.3V 10% X5R 0201")
      (fields
        (field (name "MANUFACTURER") "Yageo")
        (field (name "MANUFACTURER PART NUMBER") "CC0201KRX5R5BB105")
      )
      (libsource (lib "CC0201") (part "CC0201KRX5R5BB105"))
    )
    (comp (ref "C134")
      (value "1uF")
      (footprint "CC0201_L-R")
      (description "CAP CER 1.0 uF 6.3V 10% X5R 0201")
      (fields
        (field (name "MANUFACTURER") "Yageo")
        (field (name "MANUFACTURER PART NUMBER") "CC0201KRX5R5BB105")
      )
      (libsource (lib "CC0201") (part "CC0201KRX5R5BB105"))
    )
    (comp (ref "C135")
      (value "1uF")
      (footprint "CC0201_L-R")
      (description "CAP CER 1.0 uF 6.3V 10% X5R 0201")
      (fields
        (field (name "MANUFACTURER") "Yageo")
        (field (name "MANUFACTURER PART NUMBER") "CC0201KRX5R5BB105")
      )
      (libsource (lib "CC0201") (part "CC0201KRX5R5BB105"))
    )
    (comp (ref "C136")
      (value "1uF")
      (footprint "CC0201_L-R")
      (description "CAP CER 1.0 uF 6.3V 10% X5R 0201")
      (fields
        (field (name "MANUFACTURER") "Yageo")
        (field (name "MANUFACTURER PART NUMBER") "CC0201KRX5R5BB105")
      )
      (libsource (lib "CC0201") (part "CC0201KRX5R5BB105"))
    )
    (comp (ref "C137")
      (value "22uF")
      (footprint "CC0603_H0.8_L-R")
      (description "CAP CER 22 uF 10V 20% X5R 0603")
      (fields
        (field (name "MANUFACTURER") "Murata")
        (field (name "MANUFACTURER PART NUMBER") "GRM188R61A226ME15J")
      )
      (libsource (lib "CC0603") (part "GRM188R61A226ME15J"))
    )
    (comp (ref "C138")
      (value "1uF")
      (footprint "CC0201_L-R")
      (description "CAP CER 1.0 uF 6.3V 10% X5R 0201")
      (fields
        (field (name "MANUFACTURER") "Yageo")
        (field (name "MANUFACTURER PART NUMBER") "CC0201KRX5R5BB105")
      )
      (libsource (lib "CC0201") (part "CC0201KRX5R5BB105"))
    )
    (comp (ref "C139")
      (value "1uF")
      (footprint "CC0201_L-R")
      (description "CAP CER 1.0 uF 6.3V 10% X5R 0201")
      (fields
        (field (name "MANUFACTURER") "Yageo")
        (field (name "MANUFACTURER PART NUMBER") "CC0201KRX5R5BB105")
      )
      (libsource (lib "CC0201") (part "CC0201KRX5R5BB105"))
    )
    (comp (ref "C140")
      (value "1uF")
      (footprint "CC0201_L-R")
      (description "CAP CER 1.0 uF 6.3V 10% X5R 0201")
      (fields
        (field (name "MANUFACTURER") "Yageo")
        (field (name "MANUFACTURER PART NUMBER") "CC0201KRX5R5BB105")
      )
      (libsource (lib "CC0201") (part "CC0201KRX5R5BB105"))
    )
    (comp (ref "C141")
      (value "1uF")
      (footprint "CC0201_L-R")
      (description "CAP CER 1.0 uF 6.3V 10% X5R 0201")
      (fields
        (field (name "MANUFACTURER") "Yageo")
        (field (name "MANUFACTURER PART NUMBER") "CC0201KRX5R5BB105")
      )
      (libsource (lib "CC0201") (part "CC0201KRX5R5BB105"))
    )
    (comp (ref "C142")
      (value "1uF")
      (footprint "CC0201_L-R")
      (description "CAP CER 1.0 uF 6.3V 10% X5R 0201")
      (fields
        (field (name "MANUFACTURER") "Yageo")
        (field (name "MANUFACTURER PART NUMBER") "CC0201KRX5R5BB105")
      )
      (libsource (lib "CC0201") (part "CC0201KRX5R5BB105"))
    )
    (comp (ref "C143")
      (value "1uF")
      (footprint "CC0201_L-R")
      (description "CAP CER 1.0 uF 6.3V 10% X5R 0201")
      (fields
        (field (name "MANUFACTURER") "Yageo")
        (field (name "MANUFACTURER PART NUMBER") "CC0201KRX5R5BB105")
      )
      (libsource (lib "CC0201") (part "CC0201KRX5R5BB105"))
    )
    (comp (ref "C144")
      (value "22uF")
      (footprint "CC0603_H0.8_L-R")
      (description "CAP CER 22 uF 10V 20% X5R 0603")
      (fields
        (field (name "MANUFACTURER") "Murata")
        (field (name "MANUFACTURER PART NUMBER") "GRM188R61A226ME15J")
      )
      (libsource (lib "CC0603") (part "GRM188R61A226ME15J"))
    )
    (comp (ref "C145")
      (value "1uF")
      (footprint "CC0201_L-R")
      (description "CAP CER 1.0 uF 6.3V 10% X5R 0201")
      (fields
        (field (name "MANUFACTURER") "Yageo")
        (field (name "MANUFACTURER PART NUMBER") "CC0201KRX5R5BB105")
      )
      (libsource (lib "CC0201") (part "CC0201KRX5R5BB105"))
    )
    (comp (ref "C146")
      (value "1uF")
      (footprint "CC0201_L-R")
      (description "CAP CER 1.0 uF 6.3V 10% X5R 0201")
      (fields
        (field (name "MANUFACTURER") "Yageo")
        (field (name "MANUFACTURER PART NUMBER") "CC0201KRX5R5BB105")
      )
      (libsource (lib "CC0201") (part "CC0201KRX5R5BB105"))
    )
    (comp (ref "C147")
      (value "1uF")
      (footprint "CC0201_L-R")
      (description "CAP CER 1.0 uF 6.3V 10% X5R 0201")
      (fields
        (field (name "MANUFACTURER") "Yageo")
        (field (name "MANUFACTURER PART NUMBER") "CC0201KRX5R5BB105")
      )
      (libsource (lib "CC0201") (part "CC0201KRX5R5BB105"))
    )
    (comp (ref "C148")
      (value "1uF")
      (footprint "CC0201_L-R")
      (description "CAP CER 1.0 uF 6.3V 10% X5R 0201")
      (fields
        (field (name "MANUFACTURER") "Yageo")
        (field (name "MANUFACTURER PART NUMBER") "CC0201KRX5R5BB105")
      )
      (libsource (lib "CC0201") (part "CC0201KRX5R5BB105"))
    )
    (comp (ref "C149")
      (value "1uF")
      (footprint "CC0201_L-R")
      (description "CAP CER 1.0 uF 6.3V 10% X5R 0201")
      (fields
        (field (name "MANUFACTURER") "Yageo")
        (field (name "MANUFACTURER PART NUMBER") "CC0201KRX5R5BB105")
      )
      (libsource (lib "CC0201") (part "CC0201KRX5R5BB105"))
    )
    (comp (ref "C150")
      (value "1uF")
      (footprint "CC0201_L-R")
      (description "CAP CER 1.0 uF 6.3V 10% X5R 0201")
      (fields
        (field (name "MANUFACTURER") "Yageo")
        (field (name "MANUFACTURER PART NUMBER") "CC0201KRX5R5BB105")
      )
      (libsource (lib "CC0201") (part "CC0201KRX5R5BB105"))
    )
    (comp (ref "FB1")
      (value "240R")
      (footprint "IND0201_L-R")
      (description "FERRITE CHIP 240 OHM 350mA 0201")
      (fields
        (field (name "MANUFACTURER") "Murata")
        (field (name "MANUFACTURER PART NUMBER") "BLM03AX241SN1D")
      )
      (libsource (lib "Inductors") (part "BLM03AX241SN1D"))
    )
    (comp (ref "FB2")
      (value "120R")
      (footprint "INDC0603_L-R")
      (description "FERRITE CHIP 120 OHM 2A 0603")
      (fields
        (field (name "MANUFACTURER") "Murata")
        (field (name "MANUFACTURER PART NUMBER") "BLM18PG121SH1D")
      )
      (libsource (lib "Inductors") (part "BLM18PG121SH1D"))
    )
    (comp (ref "U1")
      (value "MIMX8MQ5DVAJZAB")
      (footprint "FCPBGA-621_NXP")
      (description "ARM Cortex-A53 Microprocessor IC i.MX8MQ 4 Core, 64-Bit 1.5GHz 621-FCPBGA (17x17)")
      (fields (field (name "MANUFACTURER") "NXP Semiconductors"))
      (libsource (lib "MCU") (part "I.MX8MQ5DVAJZAB"))
    )
    (comp (ref "U2")
      (value "MT53D1024M32D4DT-046 AIT:D")
      (footprint "VFBGA200_10x14x0.95")
      (description "DRAM Chip LPDDR4 SDRAM 32Gbit 1024M X 32 200-Ball VFBGA")
      (fields (field (name "MANUFACTURER") "Micron Technology"))
      (libsource (lib "IC_Memory") (part "MT53D1024M32D4DT"))
    )
  )
  (nets
    (net (code "1") (name "0V") (class "Default")
      (node (ref "C1") (pin "2") (pinfunction "2_2") (pintype "passive"))
      (node (ref "C10") (pin "2") (pinfunction "2_2") (pintype "passive"))
      (node (ref "C100") (pin "2") (pinfunction "2_2") (pintype "passive"))
      (node (ref "C101") (pin "2") (pinfunction "2_2") (pintype "passive"))
      (node (ref "C102") (pin "1") (pinfunction "1_1") (pintype "passive"))
      (node (ref "C103") (pin "2") (pinfunction "2_2") (pintype "passive"))
      (node (ref "C104") (pin "2") (pinfunction "2_2") (pintype "passive"))
      (node (ref "C105") (pin "2") (pinfunction "2_2") (pintype "passive"))
      (node (ref "C106") (pin "2") (pinfunction "2_2") (pintype "passive"))
      (node (ref "C107") (pin "2") (pinfunction "2_2") (pintype "passive"))
      (node (ref "C108") (pin "2") (pinfunction "2_2") (pintype "passive"))
      (node (ref "C109") (pin "2") (pinfunction "2_2") (pintype "passive"))
      (node (ref "C11") (pin "2") (pinfunction "2_2") (pintype "passive"))
      (node (ref "C110") (pin "2") (pinfunction "2_2") (pintype "passive"))
      (node (ref "C111") (pin "2") (pinfunction "2_2") (pintype "passive"))
      (node (ref "C112") (pin "2") (pinfunction "2_2") (pintype "passive"))
      (node (ref "C113") (pin "1") (pinfunction "1_1") (pintype "passive"))
      (node (ref "C114") (pin "2") (pinfunction "2_2") (pintype "passive"))
      (node (ref "C115") (pin "2") (pinfunction "2_2") (pintype "passive"))
      (node (ref "C116") (pin "2") (pinfunction "2_2") (pintype "passive"))
      (node (ref "C117") (pin "2") (pinfunction "2_2") (pintype "passive"))
      (node (ref "C118") (pin "2") (pinfunction "2_2") (pintype "passive"))
      (node (ref "C119") (pin "2") (pinfunction "2_2") (pintype "passive"))
      (node (ref "C12") (pin "2") (pinfunction "2_2") (pintype "passive"))
      (node (ref "C120") (pin "2") (pinfunction "2_2") (pintype "passive"))
      (node (ref "C121") (pin "2") (pinfunction "2_2") (pintype "passive"))
      (node (ref "C122") (pin "2") (pinfunction "2_2") (pintype "passive"))
      (node (ref "C123") (pin "2") (pinfunction "2_2") (pintype "passive"))
      (node (ref "C124") (pin "2") (pinfunction "2_2") (pintype "passive"))
      (node (ref "C125") (pin "2") (pinfunction "2_2") (pintype "passive"))
      (node (ref "C126") (pin "2") (pinfunction "2_2") (pintype "passive"))
      (node (ref "C127") (pin "2") (pinfunction "2_2") (pintype "passive"))
      (node (ref "C128") (pin "2") (pinfunction "2_2") (pintype "passive"))
      (node (ref "C129") (pin "2") (pinfunction "2_2") (pintype "passive"))
      (node (ref "C13") (pin "2") (pinfunction "2_2") (pintype "passive"))
      (node (ref "C130") (pin "2") (pinfunction "2_2") (pintype "passive"))
      (node (ref "C131") (pin "2") (pinfunction "2_2") (pintype "passive"))
      (node (ref "C132") (pin "2") (pinfunction "2_2") (pintype "passive"))
      (node (ref "C133") (pin "2") (pinfunction "2_2") (pintype "passive"))
      (node (ref "C134") (pin "2") (pinfunction "2_2") (pintype "passive"))
      (node (ref "C135") (pin "2") (pinfunction "2_2") (pintype "passive"))
      (node (ref "C136") (pin "2") (pinfunction "2_2") (pintype "passive"))
      (node (ref "C137") (pin "2") (pinfunction "2_2") (pintype "passive"))
      (node (ref "C138") (pin "2") (pinfunction "2_2") (pintype "passive"))
      (node (ref "C139") (pin "2") (pinfunction "2_2") (pintype "passive"))
      (node (ref "C14") (pin "2") (pinfunction "2_2") (pintype "passive"))
      (node (ref "C140") (pin "2") (pinfunction "2_2") (pintype "passive"))
      (node (ref "C141") (pin "2") (pinfunction "2_2") (pintype "passive"))
      (node (ref "C142") (pin "2") (pinfunction "2_2") (pintype "passive"))
      (node (ref "C143") (pin "2") (pinfunction "2_2") (pintype "passive"))
      (node (ref "C144") (pin "2") (pinfunction "2_2") (pintype "passive"))
      (node (ref "C145") (pin "2") (pinfunction "2_2") (pintype "passive"))
      (node (ref "C146") (pin "2") (pinfunction "2_2") (pintype "passive"))
      (node (ref "C147") (pin "2") (pinfunction "2_2") (pintype "passive"))
      (node (ref "C148") (pin "2") (pinfunction "2_2") (pintype "passive"))
      (node (ref "C149") (pin "2") (pinfunction "2_2") (pintype "passive"))
      (node (ref "C15") (pin "2") (pinfunction "2_2") (pintype "passive"))
      (node (ref "C150") (pin "2") (pinfunction "2_2") (pintype "passive"))
      (node (ref "C16") (pin "2") (pinfunction "2_2") (pintype "passive"))
      (node (ref "C17") (pin "2") (pinfunction "2_2") (pintype "passive"))
      (node (ref "C18") (pin "2") (pinfunction "2_2") (pintype "passive"))
      (node (ref "C19") (pin "2") (pinfunction "2_2") (pintype "passive"))
      (node (ref "C2") (pin "2") (pinfunction "2_2") (pintype "passive"))
      (node (ref "C20") (pin "2") (pinfunction "2_2") (pintype "passive"))
      (node (ref "C21") (pin "2") (pinfunction "2_2") (pintype "passive"))
      (node (ref "C22") (pin "2") (pinfunction "2_2") (pintype "passive"))
      (node (ref "C23") (pin "2") (pinfunction "2_2") (pintype "passive"))
      (node (ref "C24") (pin "2") (pinfunction "2_2") (pintype "passive"))
      (node (ref "C25") (pin "2") (pinfunction "2_2") (pintype "passive"))
      (node (ref "C26") (pin "2") (pinfunction "2_2") (pintype "passive"))
      (node (ref "C27") (pin "2") (pinfunction "2_2") (pintype "passive"))
      (node (ref "C28") (pin "2") (pinfunction "2_2") (pintype "passive"))
      (node (ref "C29") (pin "1") (pinfunction "1_1") (pintype "passive"))
      (node (ref "C3") (pin "2") (pinfunction "2_2") (pintype "passive"))
      (node (ref "C30") (pin "1") (pinfunction "1_1") (pintype "passive"))
      (node (ref "C31") (pin "1") (pinfunction "1_1") (pintype "passive"))
      (node (ref "C32") (pin "1") (pinfunction "1_1") (pintype "passive"))
      (node (ref "C33") (pin "2") (pinfunction "2_2") (pintype "passive"))
      (node (ref "C34") (pin "2") (pinfunction "2_2") (pintype "passive"))
      (node (ref "C35") (pin "2") (pinfunction "2_2") (pintype "passive"))
      (node (ref "C36") (pin "1") (pinfunction "1_1") (pintype "passive"))
      (node (ref "C37") (pin "2") (pinfunction "2_2") (pintype "passive"))
      (node (ref "C38") (pin "2") (pinfunction "2_2") (pintype "passive"))
      (node (ref "C39") (pin "2") (pinfunction "2_2") (pintype "passive"))
      (node (ref "C4") (pin "2") (pinfunction "2_2") (pintype "passive"))
      (node (ref "C40") (pin "2") (pinfunction "2_2") (pintype "passive"))
      (node (ref "C41") (pin "2") (pinfunction "2_2") (pintype "passive"))
      (node (ref "C42") (pin "2") (pinfunction "2_2") (pintype "passive"))
      (node (ref "C43") (pin "2") (pinfunction "2_2") (pintype "passive"))
      (node (ref "C44") (pin "2") (pinfunction "2_2") (pintype "passive"))
      (node (ref "C45") (pin "2") (pinfunction "2_2") (pintype "passive"))
      (node (ref "C46") (pin "1") (pinfunction "1_1") (pintype "passive"))
      (node (ref "C47") (pin "2") (pinfunction "2_2") (pintype "passive"))
      (node (ref "C48") (pin "1") (pinfunction "1_1") (pintype "passive"))
      (node (ref "C49") (pin "1") (pinfunction "1_1") (pintype "passive"))
      (node (ref "C5") (pin "2") (pinfunction "2_2") (pintype "passive"))
      (node (ref "C50") (pin "1") (pinfunction "1_1") (pintype "passive"))
      (node (ref "C51") (pin "1") (pinfunction "1_1") (pintype "passive"))
      (node (ref "C52") (pin "2") (pinfunction "2_2") (pintype "passive"))
      (node (ref "C53") (pin "2") (pinfunction "2_2") (pintype "passive"))
      (node (ref "C54") (pin "2") (pinfunction "2_2") (pintype "passive"))
      (node (ref "C55") (pin "2") (pinfunction "2_2") (pintype "passive"))
      (node (ref "C56") (pin "2") (pinfunction "2_2") (pintype "passive"))
      (node (ref "C57") (pin "2") (pinfunction "2_2") (pintype "passive"))
      (node (ref "C58") (pin "2") (pinfunction "2_2") (pintype "passive"))
      (node (ref "C59") (pin "2") (pinfunction "2_2") (pintype "passive"))
      (node (ref "C6") (pin "2") (pinfunction "2_2") (pintype "passive"))
      (node (ref "C60") (pin "1") (pinfunction "1_1") (pintype "passive"))
      (node (ref "C61") (pin "2") (pinfunction "2_2") (pintype "passive"))
      (node (ref "C62") (pin "2") (pinfunction "2_2") (pintype "passive"))
      (node (ref "C63") (pin "2") (pinfunction "2_2") (pintype "passive"))
      (node (ref "C64") (pin "2") (pinfunction "2_2") (pintype "passive"))
      (node (ref "C65") (pin "2") (pinfunction "2_2") (pintype "passive"))
      (node (ref "C66") (pin "2") (pinfunction "2_2") (pintype "passive"))
      (node (ref "C67") (pin "2") (pinfunction "2_2") (pintype "passive"))
      (node (ref "C68") (pin "2") (pinfunction "2_2") (pintype "passive"))
      (node (ref "C69") (pin "2") (pinfunction "2_2") (pintype "passive"))
      (node (ref "C7") (pin "2") (pinfunction "2_2") (pintype "passive"))
      (node (ref "C70") (pin "2") (pinfunction "2_2") (pintype "passive"))
      (node (ref "C71") (pin "2") (pinfunction "2_2") (pintype "passive"))
      (node (ref "C72") (pin "2") (pinfunction "2_2") (pintype "passive"))
      (node (ref "C73") (pin "1") (pinfunction "1_1") (pintype "passive"))
      (node (ref "C74") (pin "2") (pinfunction "2_2") (pintype "passive"))
      (node (ref "C75") (pin "1") (pinfunction "1_1") (pintype "passive"))
      (node (ref "C76") (pin "2") (pinfunction "2_2") (pintype "passive"))
      (node (ref "C77") (pin "2") (pinfunction "2_2") (pintype "passive"))
      (node (ref "C78") (pin "2") (pinfunction "2_2") (pintype "passive"))
      (node (ref "C79") (pin "2") (pinfunction "2_2") (pintype "passive"))
      (node (ref "C8") (pin "2") (pinfunction "2_2") (pintype "passive"))
      (node (ref "C80") (pin "2") (pinfunction "2_2") (pintype "passive"))
      (node (ref "C81") (pin "2") (pinfunction "2_2") (pintype "passive"))
      (node (ref "C82") (pin "2") (pinfunction "2_2") (pintype "passive"))
      (node (ref "C83") (pin "2") (pinfunction "2_2") (pintype "passive"))
      (node (ref "C84") (pin "2") (pinfunction "2_2") (pintype "passive"))
      (node (ref "C85") (pin "2") (pinfunction "2_2") (pintype "passive"))
      (node (ref "C86") (pin "2") (pinfunction "2_2") (pintype "passive"))
      (node (ref "C87") (pin "2") (pinfunction "2_2") (pintype "passive"))
      (node (ref "C88") (pin "1") (pinfunction "1_1") (pintype "passive"))
      (node (ref "C89") (pin "2") (pinfunction "2_2") (pintype "passive"))
      (node (ref "C9") (pin "2") (pinfunction "2_2") (pintype "passive"))
      (node (ref "C90") (pin "2") (pinfunction "2_2") (pintype "passive"))
      (node (ref "C91") (pin "2") (pinfunction "2_2") (pintype "passive"))
      (node (ref "C92") (pin "2") (pinfunction "2_2") (pintype "passive"))
      (node (ref "C93") (pin "2") (pinfunction "2_2") (pintype "passive"))
      (node (ref "C94") (pin "2") (pinfunction "2_2") (pintype "passive"))
      (node (ref "C95") (pin "2") (pinfunction "2_2") (pintype "passive"))
      (node (ref "C96") (pin "1") (pinfunction "1_1") (pintype "passive"))
      (node (ref "C97") (pin "1") (pinfunction "1_1") (pintype "passive"))
      (node (ref "C98") (pin "1") (pinfunction "1_1") (pintype "passive"))
      (node (ref "C99") (pin "1") (pinfunction "1_1") (pintype "passive"))
      (node (ref "U1") (pin "A2") (pinfunction "VSS12_A2") (pintype "passive"))
      (node (ref "U1") (pin "A24") (pinfunction "VSS6_A24") (pintype "passive"))
      (node (ref "U1") (pin "AA16") (pinfunction "VSS124_AA16") (pintype "passive"))
      (node (ref "U1") (pin "AA21") (pinfunction "VSS125_AA21") (pintype "passive"))
      (node (ref "U1") (pin "AA5") (pinfunction "VSS123_AA5") (pintype "passive"))
      (node (ref "U1") (pin "AB11") (pinfunction "VSS128_AB11") (pintype "passive"))
      (node (ref "U1") (pin "AB18") (pinfunction "VSS129_AB18") (pintype "passive"))
      (node (ref "U1") (pin "AB2") (pinfunction "VSS126_AB2") (pintype "passive"))
      (node (ref "U1") (pin "AB24") (pinfunction "VSS130_AB24") (pintype "passive"))
      (node (ref "U1") (pin "AB9") (pinfunction "VSS127_AB9") (pintype "passive"))
      (node (ref "U1") (pin "AC19") (pinfunction "VSS132_AC19") (pintype "passive"))
      (node (ref "U1") (pin "AC22") (pinfunction "VSS133_AC22") (pintype "passive"))
      (node (ref "U1") (pin "AC4") (pinfunction "VSS131_AC4") (pintype "passive"))
      (node (ref "U1") (pin "AD1") (pinfunction "VSS134_AD1") (pintype "passive"))
      (node (ref "U1") (pin "AD11") (pinfunction "VSS137_AD11") (pintype "passive"))
      (node (ref "U1") (pin "AD13") (pinfunction "VSS138_AD13") (pintype "passive"))
      (node (ref "U1") (pin "AD16") (pinfunction "VSS139_AD16") (pintype "passive"))
      (node (ref "U1") (pin "AD25") (pinfunction "VSS140_AD25") (pintype "passive"))
      (node (ref "U1") (pin "AD7") (pinfunction "VSS135_AD7") (pintype "passive"))
      (node (ref "U1") (pin "AD9") (pinfunction "VSS136_AD9") (pintype "passive"))
      (node (ref "U1") (pin "AE2") (pinfunction "VSS141_AE2") (pintype "passive"))
      (node (ref "U1") (pin "AE21") (pinfunction "VSS88_AE21") (pintype "passive"))
      (node (ref "U1") (pin "AE24") (pinfunction "VSS96_AE24") (pintype "passive"))
      (node (ref "U1") (pin "AE5") (pinfunction "VSS87_AE5") (pintype "passive"))
      (node (ref "U1") (pin "B1") (pinfunction "VSS43_B1") (pintype "passive"))
      (node (ref "U1") (pin "B25") (pinfunction "VSS1_B25") (pintype "passive"))
      (node (ref "U1") (pin "C10") (pinfunction "VSS3_C10") (pintype "passive"))
      (node (ref "U1") (pin "C13") (pinfunction "VSS4_C13") (pintype "passive"))
      (node (ref "U1") (pin "C15") (pinfunction "VSS5_C15") (pintype "passive"))
      (node (ref "U1") (pin "C24") (pinfunction "VSS7_C24") (pintype "passive"))
      (node (ref "U1") (pin "C8") (pinfunction "VSS2_C8") (pintype "passive"))
      (node (ref "U1") (pin "D10") (pinfunction "VSS8_D10") (pintype "passive"))
      (node (ref "U1") (pin "D13") (pinfunction "VSS9_D13") (pintype "passive"))
      (node (ref "U1") (pin "D15") (pinfunction "VSS10_D15") (pintype "passive"))
      (node (ref "U1") (pin "D23") (pinfunction "VSS11_D23") (pintype "passive"))
      (node (ref "U1") (pin "E10") (pinfunction "VSS14_E10") (pintype "passive"))
      (node (ref "U1") (pin "E13") (pinfunction "VSS15_E13") (pintype "passive"))
      (node (ref "U1") (pin "E14") (pinfunction "VSS16_E14") (pintype "passive"))
      (node (ref "U1") (pin "E16") (pinfunction "VSS18_E16") (pintype "passive"))
      (node (ref "U1") (pin "E19") (pinfunction "VSS19_E19") (pintype "passive"))
      (node (ref "U1") (pin "E20") (pinfunction "VSS17_E20") (pintype "passive"))
      (node (ref "U1") (pin "E21") (pinfunction "VSS20_E21") (pintype "passive"))
      (node (ref "U1") (pin "E22") (pinfunction "VSS21_E22") (pintype "passive"))
      (node (ref "U1") (pin "E23") (pinfunction "VSS22_E23") (pintype "passive"))
      (node (ref "U1") (pin "E4") (pinfunction "VSS13_E4") (pintype "passive"))
      (node (ref "U1") (pin "F10") (pinfunction "VSS23_F10") (pintype "passive"))
      (node (ref "U1") (pin "F13") (pinfunction "VSS24_F13") (pintype "passive"))
      (node (ref "U1") (pin "F14") (pinfunction "VSS25_F14") (pintype "passive"))
      (node (ref "U1") (pin "F16") (pinfunction "VSS27_F16") (pintype "passive"))
      (node (ref "U1") (pin "F20") (pinfunction "VSS26_F20") (pintype "passive"))
      (node (ref "U1") (pin "G10") (pinfunction "VSS29_G10") (pintype "passive"))
      (node (ref "U1") (pin "G13") (pinfunction "VSS30_G13") (pintype "passive"))
      (node (ref "U1") (pin "G17") (pinfunction "VSS31_G17") (pintype "passive"))
      (node (ref "U1") (pin "G18") (pinfunction "VSS32_G18") (pintype "passive"))
      (node (ref "U1") (pin "G24") (pinfunction "VSS33_G24") (pintype "passive"))
      (node (ref "U1") (pin "G9") (pinfunction "VSS28_G9") (pintype "passive"))
      (node (ref "U1") (pin "H10") (pinfunction "VSS36_H10") (pintype "passive"))
      (node (ref "U1") (pin "H11") (pinfunction "VSS37_H11") (pintype "passive"))
      (node (ref "U1") (pin "H12") (pinfunction "VSS38_H12") (pintype "passive"))
      (node (ref "U1") (pin "H13") (pinfunction "VSS39_H13") (pintype "passive"))
      (node (ref "U1") (pin "H17") (pinfunction "VSS40_H17") (pintype "passive"))
      (node (ref "U1") (pin "H18") (pinfunction "VSS41_H18") (pintype "passive"))
      (node (ref "U1") (pin "H8") (pinfunction "VSS34_H8") (pintype "passive"))
      (node (ref "U1") (pin "H9") (pinfunction "VSS35_H9") (pintype "passive"))
      (node (ref "U1") (pin "J11") (pinfunction "VSS45_J11") (pintype "passive"))
      (node (ref "U1") (pin "J12") (pinfunction "VSS46_J12") (pintype "passive"))
      (node (ref "U1") (pin "J13") (pinfunction "VSS47_J13") (pintype "passive"))
      (node (ref "U1") (pin "J14") (pinfunction "VSS48_J14") (pintype "passive"))
      (node (ref "U1") (pin "J17") (pinfunction "VSS49_J17") (pintype "passive"))
      (node (ref "U1") (pin "J18") (pinfunction "VSS50_J18") (pintype "passive"))
      (node (ref "U1") (pin "J19") (pinfunction "VSS51_J19") (pintype "passive"))
      (node (ref "U1") (pin "J3") (pinfunction "VSS42_J3") (pintype "passive"))
      (node (ref "U1") (pin "J8") (pinfunction "VSS44_J8") (pintype "passive"))
      (node (ref "U1") (pin "K11") (pinfunction "VSS53_K11") (pintype "passive"))
      (node (ref "U1") (pin "K13") (pinfunction "VSSA_FPLL_ARM_K13") (pintype "passive"))
      (node (ref "U1") (pin "K17") (pinfunction "VSS55_K17") (pintype "passive"))
      (node (ref "U1") (pin "K18") (pinfunction "VSS56_K18") (pintype "passive"))
      (node (ref "U1") (pin "K23") (pinfunction "VSS57_K23") (pintype "passive"))
      (node (ref "U1") (pin "K8") (pinfunction "VSS52_K8") (pintype "passive"))
      (node (ref "U1") (pin "L11") (pinfunction "VSS59_L11") (pintype "passive"))
      (node (ref "U1") (pin "L14") (pinfunction "VSS60_L14") (pintype "passive"))
      (node (ref "U1") (pin "L17") (pinfunction "VSS61_L17") (pintype "passive"))
      (node (ref "U1") (pin "L8") (pinfunction "VSS58_L8") (pintype "passive"))
      (node (ref "U1") (pin "M11") (pinfunction "VSS63_M11") (pintype "passive"))
      (node (ref "U1") (pin "M14") (pinfunction "VSS64_M14") (pintype "passive"))
      (node (ref "U1") (pin "M17") (pinfunction "VSS65_M17") (pintype "passive"))
      (node (ref "U1") (pin "M8") (pinfunction "VSS62_M8") (pintype "passive"))
      (node (ref "U1") (pin "N12") (pinfunction "VSSA_SPLL_VIDEO2_N12") (pintype "passive"))
      (node (ref "U1") (pin "N14") (pinfunction "VSS68_N14") (pintype "passive"))
      (node (ref "U1") (pin "N15") (pinfunction "VSS74_N15") (pintype "passive"))
      (node (ref "U1") (pin "N16") (pinfunction "VSS73_N16") (pintype "passive"))
      (node (ref "U1") (pin "N17") (pinfunction "VSS67_N17") (pintype "passive"))
      (node (ref "U1") (pin "N18") (pinfunction "VSS54_N18") (pintype "passive"))
      (node (ref "U1") (pin "N3") (pinfunction "VSS66_N3") (pintype "passive"))
      (node (ref "U1") (pin "P11") (pinfunction "VSS71_P11") (pintype "passive"))
      (node (ref "U1") (pin "P14") (pinfunction "VSS72_P14") (pintype "passive"))
      (node (ref "U1") (pin "P17") (pinfunction "VSS75_P17") (pintype "passive"))
      (node (ref "U1") (pin "P18") (pinfunction "VSS76_P18") (pintype "passive"))
      (node (ref "U1") (pin "P23") (pinfunction "VSS77_P23") (pintype "passive"))
      (node (ref "U1") (pin "P6") (pinfunction "VSS69_P6") (pintype "passive"))
      (node (ref "U1") (pin "P8") (pinfunction "VSS70_P8") (pintype "passive"))
      (node (ref "U1") (pin "R7") (pinfunction "VSS78_R7") (pintype "passive"))
      (node (ref "U1") (pin "T10") (pinfunction "VSS83_T10") (pintype "passive"))
      (node (ref "U1") (pin "T11") (pinfunction "VSS84_T11") (pintype "passive"))
      (node (ref "U1") (pin "T12") (pinfunction "VSS85_T12") (pintype "passive"))
      (node (ref "U1") (pin "T13") (pinfunction "VSS86_T13") (pintype "passive"))
      (node (ref "U1") (pin "T14") (pinfunction "VSSA_SPLL_DRAM_T14") (pintype "passive"))
      (node (ref "U1") (pin "T3") (pinfunction "VSS80_T3") (pintype "passive"))
      (node (ref "U1") (pin "T4") (pinfunction "VSS81_T4") (pintype "passive"))
      (node (ref "U1") (pin "T9") (pinfunction "VSS82_T9") (pintype "passive"))
      (node (ref "U1") (pin "U15") (pinfunction "VSS91_U15") (pintype "passive"))
      (node (ref "U1") (pin "U16") (pinfunction "VSSA_FPLL_U16") (pintype "passive"))
      (node (ref "U1") (pin "U18") (pinfunction "VSS92_U18") (pintype "passive"))
      (node (ref "U1") (pin "U8") (pinfunction "VSS89_U8") (pintype "passive"))
      (node (ref "U1") (pin "U9") (pinfunction "VSS90_U9") (pintype "passive"))
      (node (ref "U1") (pin "V16") (pinfunction "VSS95_V16") (pintype "passive"))
      (node (ref "U1") (pin "V17") (pinfunction "VSSA_SPLL_V17") (pintype "passive"))
      (node (ref "U1") (pin "V23") (pinfunction "VSSA_XTAL_25M_V23") (pintype "passive"))
      (node (ref "U1") (pin "V4") (pinfunction "VSS93_V4") (pintype "passive"))
      (node (ref "U1") (pin "V8") (pinfunction "VSS94_V8") (pintype "passive"))
      (node (ref "U1") (pin "W1") (pinfunction "VSS97_W1") (pintype "passive"))
      (node (ref "U1") (pin "W10") (pinfunction "VSS100_W10") (pintype "passive"))
      (node (ref "U1") (pin "W11") (pinfunction "VSS101_W11") (pintype "passive"))
      (node (ref "U1") (pin "W12") (pinfunction "VSS102_W12") (pintype "passive"))
      (node (ref "U1") (pin "W13") (pinfunction "VSS103_W13") (pintype "passive"))
      (node (ref "U1") (pin "W14") (pinfunction "VSS104_W14") (pintype "passive"))
      (node (ref "U1") (pin "W15") (pinfunction "VSS105_W15") (pintype "passive"))
      (node (ref "U1") (pin "W16") (pinfunction "VSS106_W16") (pintype "passive"))
      (node (ref "U1") (pin "W22") (pinfunction "VSSA_XTAL_27M_W22") (pintype "passive"))
      (node (ref "U1") (pin "W25") (pinfunction "VSS107_W25") (pintype "passive"))
      (node (ref "U1") (pin "W7") (pinfunction "VSS98_W7") (pintype "passive"))
      (node (ref "U1") (pin "W8") (pinfunction "VSS99_W8") (pintype "passive"))
      (node (ref "U1") (pin "W9") (pinfunction "VSS79_W9") (pintype "passive"))
      (node (ref "U1") (pin "Y11") (pinfunction "VSS114_Y11") (pintype "passive"))
      (node (ref "U1") (pin "Y13") (pinfunction "VSS115_Y13") (pintype "passive"))
      (node (ref "U1") (pin "Y15") (pinfunction "VSS116_Y15") (pintype "passive"))
      (node (ref "U1") (pin "Y17") (pinfunction "VSS117_Y17") (pintype "passive"))
      (node (ref "U1") (pin "Y19") (pinfunction "VSS118_Y19") (pintype "passive"))
      (node (ref "U1") (pin "Y2") (pinfunction "VSS108_Y2") (pintype "passive"))
      (node (ref "U1") (pin "Y21") (pinfunction "VSS119_Y21") (pintype "passive"))
      (node (ref "U1") (pin "Y22") (pinfunction "VSS120_Y22") (pintype "passive"))
      (node (ref "U1") (pin "Y23") (pinfunction "VSS121_Y23") (pintype "passive"))
      (node (ref "U1") (pin "Y24") (pinfunction "VSS122_Y24") (pintype "passive"))
      (node (ref "U1") (pin "Y3") (pinfunction "VSS109_Y3") (pintype "passive"))
      (node (ref "U1") (pin "Y4") (pinfunction "VSS110_Y4") (pintype "passive"))
      (node (ref "U1") (pin "Y5") (pinfunction "VSS111_Y5") (pintype "passive"))
      (node (ref "U1") (pin "Y7") (pinfunction "VSS112_Y7") (pintype "passive"))
      (node (ref "U1") (pin "Y9") (pinfunction "VSS113_Y9") (pintype "passive"))
      (node (ref "U2") (pin "A10") (pinfunction "VSS_A10_A10") (pintype "power_in"))
      (node (ref "U2") (pin "A3") (pinfunction "VSS_A3_A3") (pintype "power_in"))
      (node (ref "U2") (pin "AB10") (pinfunction "VSS_AB10_AB10") (pintype "power_in"))
      (node (ref "U2") (pin "AB3") (pinfunction "VSS_AB3_AB3") (pintype "power_in"))
      (node (ref "U2") (pin "AB5") (pinfunction "VSS_AB5_AB5") (pintype "power_in"))
      (node (ref "U2") (pin "AB8") (pinfunction "VSS_AB8_AB8") (pintype "power_in"))
      (node (ref "U2") (pin "C1") (pinfunction "VSS_C1_C1") (pintype "power_in"))
      (node (ref "U2") (pin "C12") (pinfunction "VSS_C12_C12") (pintype "power_in"))
      (node (ref "U2") (pin "C5") (pinfunction "VSS_C5_C5") (pintype "power_in"))
      (node (ref "U2") (pin "C8") (pinfunction "VSS_C8_C8") (pintype "power_in"))
      (node (ref "U2") (pin "D11") (pinfunction "VSS_D11_D11") (pintype "power_in"))
      (node (ref "U2") (pin "D2") (pinfunction "VSS_D2_D2") (pintype "power_in"))
      (node (ref "U2") (pin "D4") (pinfunction "VSS_D4_D4") (pintype "power_in"))
      (node (ref "U2") (pin "D9") (pinfunction "VSS_D9_D9") (pintype "power_in"))
      (node (ref "U2") (pin "E1") (pinfunction "VSS_E1_E1") (pintype "power_in"))
      (node (ref "U2") (pin "E12") (pinfunction "VSS_E12_E12") (pintype "power_in"))
      (node (ref "U2") (pin "E5") (pinfunction "VSS_E5_E5") (pintype "power_in"))
      (node (ref "U2") (pin "E8") (pinfunction "VSS_E8_E8") (pintype "power_in"))
      (node (ref "U2") (pin "G1") (pinfunction "VSS_G1_G1") (pintype "power_in"))
      (node (ref "U2") (pin "G10") (pinfunction "VSS_G10_G10") (pintype "power_in"))
      (node (ref "U2") (pin "G12") (pinfunction "VSS_G12_G12") (pintype "power_in"))
      (node (ref "U2") (pin "G3") (pinfunction "VSS_G3_G3") (pintype "power_in"))
      (node (ref "U2") (pin "G5") (pinfunction "VSS_G5_G5") (pintype "power_in"))
      (node (ref "U2") (pin "G8") (pinfunction "VSS_G8_G8") (pintype "power_in"))
      (node (ref "U2") (pin "J1") (pinfunction "VSS_J1_J1") (pintype "power_in"))
      (node (ref "U2") (pin "J10") (pinfunction "VSS_J10_J10") (pintype "power_in"))
      (node (ref "U2") (pin "J12") (pinfunction "VSS_J12_J12") (pintype "power_in"))
      (node (ref "U2") (pin "J3") (pinfunction "VSS_J3_J3") (pintype "power_in"))
      (node (ref "U2") (pin "K11") (pinfunction "VSS_K11_K11") (pintype "power_in"))
      (node (ref "U2") (pin "K2") (pinfunction "VSS_K2_K2") (pintype "power_in"))
      (node (ref "U2") (pin "K4") (pinfunction "VSS_K4_K4") (pintype "power_in"))
      (node (ref "U2") (pin "K9") (pinfunction "VSS_K9_K9") (pintype "power_in"))
      (node (ref "U2") (pin "N11") (pinfunction "VSS_N11_N11") (pintype "power_in"))
      (node (ref "U2") (pin "N2") (pinfunction "VSS_N2_N2") (pintype "power_in"))
      (node (ref "U2") (pin "N4") (pinfunction "VSS_N4_N4") (pintype "power_in"))
      (node (ref "U2") (pin "N9") (pinfunction "VSS_N9_N9") (pintype "power_in"))
      (node (ref "U2") (pin "P1") (pinfunction "VSS_P1_P1") (pintype "power_in"))
      (node (ref "U2") (pin "P10") (pinfunction "VSS_P10_P10") (pintype "power_in"))
      (node (ref "U2") (pin "P12") (pinfunction "VSS_P12_P12") (pintype "power_in"))
      (node (ref "U2") (pin "P3") (pinfunction "VSS_P3_P3") (pintype "power_in"))
      (node (ref "U2") (pin "T1") (pinfunction "VSS_T1_T1") (pintype "power_in"))
      (node (ref "U2") (pin "T10") (pinfunction "VSS_T10_T10") (pintype "power_in"))
      (node (ref "U2") (pin "T12") (pinfunction "VSS_T12_T12") (pintype "power_in"))
      (node (ref "U2") (pin "T3") (pinfunction "VSS_T3_T3") (pintype "power_in"))
      (node (ref "U2") (pin "T5") (pinfunction "VSS_T5_T5") (pintype "power_in"))
      (node (ref "U2") (pin "T8") (pinfunction "VSS_T8_T8") (pintype "power_in"))
      (node (ref "U2") (pin "V1") (pinfunction "VSS_V1_V1") (pintype "power_in"))
      (node (ref "U2") (pin "V12") (pinfunction "VSS_V12_V12") (pintype "power_in"))
      (node (ref "U2") (pin "V5") (pinfunction "VSS_V5_V5") (pintype "power_in"))
      (node (ref "U2") (pin "V8") (pinfunction "VSS_V8_V8") (pintype "power_in"))
      (node (ref "U2") (pin "W11") (pinfunction "VSS_W11_W11") (pintype "power_in"))
      (node (ref "U2") (pin "W2") (pinfunction "VSS_W2_W2") (pintype "power_in"))
      (node (ref "U2") (pin "W4") (pinfunction "VSS_W4_W4") (pintype "power_in"))
      (node (ref "U2") (pin "W9") (pinfunction "VSS_W9_W9") (pintype "power_in"))
      (node (ref "U2") (pin "Y1") (pinfunction "VSS_Y1_Y1") (pintype "power_in"))
      (node (ref "U2") (pin "Y12") (pinfunction "VSS_Y12_Y12") (pintype "power_in"))
      (node (ref "U2") (pin "Y5") (pinfunction "VSS_Y5_Y5") (pintype "power_in"))
      (node (ref "U2") (pin "Y8") (pinfunction "VSS_Y8_Y8") (pintype "power_in"))
    )
    (net (code "2") (name "NVCC_3V3") (class "Default")
      (node (ref "C1") (pin "1") (pinfunction "1_1") (pintype "passive"))
      (node (ref "C10") (pin "1") (pinfunction "1_1") (pintype "passive"))
      (node (ref "C11") (pin "1") (pinfunction "1_1") (pintype "passive"))
      (node (ref "C2") (pin "1") (pinfunction "1_1") (pintype "passive"))
      (node (ref "C3") (pin "1") (pinfunction "1_1") (pintype "passive"))
      (node (ref "C4") (pin "1") (pinfunction "1_1") (pintype "passive"))
      (node (ref "C7") (pin "1") (pinfunction "1_1") (pintype "passive"))
      (node (ref "C8") (pin "1") (pinfunction "1_1") (pintype "passive"))
      (node (ref "C9") (pin "1") (pinfunction "1_1") (pintype "passive"))
      (node (ref "U1") (pin "D8") (pinfunction "NVCC_UART_D8") (pintype "passive"))
      (node (ref "U1") (pin "E3") (pinfunction "NVCC_SAI3_E3") (pintype "passive"))
      (node (ref "U1") (pin "F5") (pinfunction "NVCC_ECSPI_F5") (pintype "passive"))
      (node (ref "U1") (pin "H7") (pinfunction "NVCC_I2C_H7") (pintype "passive"))
      (node (ref "U1") (pin "J7") (pinfunction "NVCC_SAI2_J7") (pintype "passive"))
      (node (ref "U1") (pin "K3") (pinfunction "NVCC_SAI1_2_K3") (pintype "passive"))
      (node (ref "U1") (pin "L18") (pinfunction "NVCC_NAND1_L18") (pintype "passive"))
      (node (ref "U1") (pin "L3") (pinfunction "NVCC_SAI1_1_L3") (pintype "passive"))
      (node (ref "U1") (pin "M18") (pinfunction "NVCC_NAND2_M18") (pintype "passive"))
      (node (ref "U1") (pin "M3") (pinfunction "NVCC_SAI5_M3") (pintype "passive"))
      (node (ref "U1") (pin "R5") (pinfunction "NVCC_GPIO1_R5") (pintype "passive"))
      (node (ref "U1") (pin "R6") (pinfunction "NVCC_GPIO2_R6") (pintype "passive"))
      (node (ref "U1") (pin "W4") (pinfunction "NVCC_JTAG_W4") (pintype "passive"))
    )
    (net (code "3") (name "NVCC_DRAM_1V1") (class "Default")
      (node (ref "C130") (pin "1") (pinfunction "1_1") (pintype "passive"))
      (node (ref "C131") (pin "1") (pinfunction "1_1") (pintype "passive"))
      (node (ref "C132") (pin "1") (pinfunction "1_1") (pintype "passive"))
      (node (ref "C133") (pin "1") (pinfunction "1_1") (pintype "passive"))
      (node (ref "C134") (pin "1") (pinfunction "1_1") (pintype "passive"))
      (node (ref "C135") (pin "1") (pinfunction "1_1") (pintype "passive"))
      (node (ref "C136") (pin "1") (pinfunction "1_1") (pintype "passive"))
      (node (ref "C137") (pin "1") (pinfunction "1_1") (pintype "passive"))
      (node (ref "C138") (pin "1") (pinfunction "1_1") (pintype "passive"))
      (node (ref "C139") (pin "1") (pinfunction "1_1") (pintype "passive"))
      (node (ref "C140") (pin "1") (pinfunction "1_1") (pintype "passive"))
      (node (ref "C141") (pin "1") (pinfunction "1_1") (pintype "passive"))
      (node (ref "C142") (pin "1") (pinfunction "1_1") (pintype "passive"))
      (node (ref "C143") (pin "1") (pinfunction "1_1") (pintype "passive"))
      (node (ref "C144") (pin "1") (pinfunction "1_1") (pintype "passive"))
      (node (ref "C145") (pin "1") (pinfunction "1_1") (pintype "passive"))
      (node (ref "C146") (pin "1") (pinfunction "1_1") (pintype "passive"))
      (node (ref "C147") (pin "1") (pinfunction "1_1") (pintype "passive"))
      (node (ref "C148") (pin "1") (pinfunction "1_1") (pintype "passive"))
      (node (ref "C149") (pin "1") (pinfunction "1_1") (pintype "passive"))
      (node (ref "C150") (pin "1") (pinfunction "1_1") (pintype "passive"))
      (node (ref "C28") (pin "1") (pinfunction "1_1") (pintype "passive"))
      (node (ref "C29") (pin "2") (pinfunction "2_2") (pintype "passive"))
      (node (ref "C30") (pin "2") (pinfunction "2_2") (pintype "passive"))
      (node (ref "C31") (pin "2") (pinfunction "2_2") (pintype "passive"))
      (node (ref "C32") (pin "2") (pinfunction "2_2") (pintype "passive"))
      (node (ref "C33") (pin "1") (pinfunction "1_1") (pintype "passive"))
      (node (ref "C47") (pin "1") (pinfunction "1_1") (pintype "passive"))
      (node (ref "C48") (pin "2") (pinfunction "2_2") (pintype "passive"))
      (node (ref "C49") (pin "2") (pinfunction "2_2") (pintype "passive"))
      (node (ref "C50") (pin "2") (pinfunction "2_2") (pintype "passive"))
      (node (ref "C51") (pin "2") (pinfunction "2_2") (pintype "passive"))
      (node (ref "C52") (pin "1") (pinfunction "1_1") (pintype "passive"))
      (node (ref "U1") (pin "AA10") (pinfunction "NVCC_DRAM2_AA10") (pintype "passive"))
      (node (ref "U1") (pin "AA15") (pinfunction "NVCC_DRAM4_AA15") (pintype "passive"))
      (node (ref "U1") (pin "AB17") (pinfunction "NVCC_DRAM3_AB17") (pintype "passive"))
      (node (ref "U1") (pin "AB23") (pinfunction "NVCC_DRAM1_AB23") (pintype "passive"))
      (node (ref "U1") (pin "AB3") (pinfunction "NVCC_DRAM6_AB3") (pintype "passive"))
      (node (ref "U1") (pin "AB8") (pinfunction "NVCC_DRAM5_AB8") (pintype "passive"))
      (node (ref "U1") (pin "AC14") (pinfunction "NVCC_DRAM7_AC14") (pintype "passive"))
      (node (ref "U1") (pin "AC17") (pinfunction "NVCC_DRAM8_AC17") (pintype "passive"))
      (node (ref "U1") (pin "AC20") (pinfunction "NVCC_DRAM9_AC20") (pintype "passive"))
      (node (ref "U1") (pin "AC23") (pinfunction "NVCC_DRAM11_AC23") (pintype "passive"))
      (node (ref "U1") (pin "AC3") (pinfunction "NVCC_DRAM10_AC3") (pintype "passive"))
      (node (ref "U1") (pin "AC6") (pinfunction "NVCC_DRAM13_AC6") (pintype "passive"))
      (node (ref "U1") (pin "AC8") (pinfunction "NVCC_DRAM12_AC8") (pintype "passive"))
      (node (ref "U1") (pin "AD18") (pinfunction "NVCC_DRAM15_AD18") (pintype "passive"))
      (node (ref "U1") (pin "AD21") (pinfunction "NVCC_DRAM14_AD21") (pintype "passive"))
      (node (ref "U1") (pin "AD5") (pinfunction "NVCC_DRAM16_AD5") (pintype "passive"))
      (node (ref "U1") (pin "Y12") (pinfunction "NVCC_DRAM18_Y12") (pintype "passive"))
      (node (ref "U1") (pin "Y14") (pinfunction "NVCC_DRAM17_Y14") (pintype "passive"))
      (node (ref "U2") (pin "A4") (pinfunction "VDD2_A4_A4") (pintype "power_in"))
      (node (ref "U2") (pin "A9") (pinfunction "VDD2_A9_A9") (pintype "power_in"))
      (node (ref "U2") (pin "AA10") (pinfunction "VDDQ_AA10_AA10") (pintype "power_in"))
      (node (ref "U2") (pin "AA3") (pinfunction "VDDQ_AA3_AA3") (pintype "power_in"))
      (node (ref "U2") (pin "AA5") (pinfunction "VDDQ_AA5_AA5") (pintype "power_in"))
      (node (ref "U2") (pin "AA8") (pinfunction "VDDQ_AA8_AA8") (pintype "power_in"))
      (node (ref "U2") (pin "AB4") (pinfunction "VDD2_AB4_AB4") (pintype "power_in"))
      (node (ref "U2") (pin "AB9") (pinfunction "VDD2_AB9_AB9") (pintype "power_in"))
      (node (ref "U2") (pin "B10") (pinfunction "VDDQ_B10_B10") (pintype "power_in"))
      (node (ref "U2") (pin "B3") (pinfunction "VDDQ_B3_B3") (pintype "power_in"))
      (node (ref "U2") (pin "B5") (pinfunction "VDDQ_B5_B5") (pintype "power_in"))
      (node (ref "U2") (pin "B8") (pinfunction "VDDQ_B8_B8") (pintype "power_in"))
      (node (ref "U2") (pin "D1") (pinfunction "VDDQ_D1_D1") (pintype "power_in"))
      (node (ref "U2") (pin "D12") (pinfunction "VDDQ_D12_D12") (pintype "power_in"))
      (node (ref "U2") (pin "D5") (pinfunction "VDDQ_D5_D5") (pintype "power_in"))
      (node (ref "U2") (pin "D8") (pinfunction "VDDQ_D8_D8") (pintype "power_in"))
      (node (ref "U2") (pin "F10") (pinfunction "VDDQ_F10_F10") (pintype "power_in"))
      (node (ref "U2") (pin "F3") (pinfunction "VDDQ_F3_F3") (pintype "power_in"))
      (node (ref "U2") (pin "F5") (pinfunction "VDD2_F5_F5") (pintype "power_in"))
      (node (ref "U2") (pin "F8") (pinfunction "VDD2_F8_F8") (pintype "power_in"))
      (node (ref "U2") (pin "H1") (pinfunction "VDD2_H1_H1") (pintype "power_in"))
      (node (ref "U2") (pin "H12") (pinfunction "VDD2_H12_H12") (pintype "power_in"))
      (node (ref "U2") (pin "H5") (pinfunction "VDD2_H5_H5") (pintype "power_in"))
      (node (ref "U2") (pin "H8") (pinfunction "VDD2_H8_H8") (pintype "power_in"))
      (node (ref "U2") (pin "K1") (pinfunction "VDD2_K1_K1") (pintype "power_in"))
      (node (ref "U2") (pin "K10") (pinfunction "VDD2_K10_K10") (pintype "power_in"))
      (node (ref "U2") (pin "K12") (pinfunction "VDD2_K12_K12") (pintype "power_in"))
      (node (ref "U2") (pin "K3") (pinfunction "VDD2_K3_K3") (pintype "power_in"))
      (node (ref "U2") (pin "N1") (pinfunction "VDD2_N1_N1") (pintype "power_in"))
      (node (ref "U2") (pin "N10") (pinfunction "VDD2_N10_N10") (pintype "power_in"))
      (node (ref "U2") (pin "N12") (pinfunction "VDD2_N12_N12") (pintype "power_in"))
      (node (ref "U2") (pin "N3") (pinfunction "VDD2_N3_N3") (pintype "power_in"))
      (node (ref "U2") (pin "R1") (pinfunction "VDD2_R1_R1") (pintype "power_in"))
      (node (ref "U2") (pin "R12") (pinfunction "VDD2_R12_R12") (pintype "power_in"))
      (node (ref "U2") (pin "R5") (pinfunction "VDD2_R5_R5") (pintype "power_in"))
      (node (ref "U2") (pin "R8") (pinfunction "VDD2_R8_R8") (pintype "power_in"))
      (node (ref "U2") (pin "U10") (pinfunction "VDDQ_U10_U10") (pintype "power_in"))
      (node (ref "U2") (pin "U3") (pinfunction "VDDQ_U3_U3") (pintype "power_in"))
      (node (ref "U2") (pin "U5") (pinfunction "VDD2_U5_U5") (pintype "power_in"))
      (node (ref "U2") (pin "U8") (pinfunction "VDD2_U8_U8") (pintype "power_in"))
      (node (ref "U2") (pin "W1") (pinfunction "VDDQ_W1_W1") (pintype "power_in"))
      (node (ref "U2") (pin "W12") (pinfunction "VDDQ_W12_W12") (pintype "power_in"))
      (node (ref "U2") (pin "W5") (pinfunction "VDDQ_W5_W5") (pintype "power_in"))
      (node (ref "U2") (pin "W8") (pinfunction "VDDQ_W8_W8") (pintype "power_in"))
    )
    (net (code "4") (name "NVCC_ENET_2V5") (class "Default")
      (node (ref "C26") (pin "1") (pinfunction "1_1") (pintype "passive"))
      (node (ref "U1") (pin "T18") (pinfunction "NVCC_ENET_T18") (pintype "passive"))
    )
    (net (code "5") (name "NVCC_SD1_1V8") (class "Default")
      (node (ref "C25") (pin "1") (pinfunction "1_1") (pintype "passive"))
      (node (ref "U1") (pin "L23") (pinfunction "NVCC_SD1_2_L23") (pintype "passive"))
      (node (ref "U1") (pin "M23") (pinfunction "NVCC_SD1_1_M23") (pintype "passive"))
    )
    (net (code "6") (name "NVCC_SD2") (class "Default")
      (node (ref "C27") (pin "1") (pinfunction "1_1") (pintype "passive"))
      (node (ref "U1") (pin "N23") (pinfunction "NVCC_SD2_N23") (pintype "passive"))
    )
    (net (code "7") (name "NVCC_SNVS_3V3") (class "Default")
      (node (ref "C6") (pin "1") (pinfunction "1_1") (pintype "passive"))
      (node (ref "U1") (pin "W18") (pinfunction "NVCC_SNVS_W18") (pintype "passive"))
    )
    (net (code "8") (name "Net-(U1M-MIPI_VDD1)") (class "Default")
      (node (ref "C121") (pin "1") (pinfunction "1_1") (pintype "passive"))
      (node (ref "C122") (pin "1") (pinfunction "1_1") (pintype "passive"))
      (node (ref "FB2") (pin "1") (pinfunction "1_1") (pintype "passive"))
      (node (ref "U1") (pin "E15") (pinfunction "MIPI_VDD1_E15") (pintype "passive"))
      (node (ref "U1") (pin "F15") (pinfunction "MIPI_VDD2_F15") (pintype "passive"))
    )
    (net (code "9") (name "Net-(U1M-VDDA_0P9)") (class "Default")
      (node (ref "C37") (pin "1") (pinfunction "1_1") (pintype "passive"))
      (node (ref "FB1") (pin "1") (pinfunction "1_1") (pintype "passive"))
      (node (ref "U1") (pin "V18") (pinfunction "VDDA_0P9_V18") (pintype "passive"))
    )
    (net (code "10") (name "VDDA_DRAM_1V8") (class "Default")
      (node (ref "C123") (pin "1") (pinfunction "1_1") (pintype "passive"))
      (node (ref "C124") (pin "1") (pinfunction "1_1") (pintype "passive"))
      (node (ref "C125") (pin "1") (pinfunction "1_1") (pintype "passive"))
      (node (ref "C126") (pin "1") (pinfunction "1_1") (pintype "passive"))
      (node (ref "C127") (pin "1") (pinfunction "1_1") (pintype "passive"))
      (node (ref "C128") (pin "1") (pinfunction "1_1") (pintype "passive"))
      (node (ref "C129") (pin "1") (pinfunction "1_1") (pintype "passive"))
      (node (ref "U1") (pin "AA11") (pinfunction "VDDA_DRAM_AA11") (pintype "passive"))
      (node (ref "U1") (pin "K14") (pinfunction "VDDA_1P8_FPLL_ARM_K14") (pintype "passive"))
      (node (ref "U1") (pin "N11") (pinfunction "VDDA_1P8_SPLL_VIDEO2_N11") (pintype "passive"))
      (node (ref "U1") (pin "R17") (pinfunction "EFUSE_VQPS_R17") (pintype "passive"))
      (node (ref "U1") (pin "T15") (pinfunction "VDDA_1P8_SPLL_DRAM_T15") (pintype "passive"))
      (node (ref "U1") (pin "T16") (pinfunction "VDDA_1P8_TSENSOR_T16") (pintype "passive"))
      (node (ref "U1") (pin "U17") (pinfunction "VDDA_1P8_FPLL_U17") (pintype "passive"))
      (node (ref "U1") (pin "U23") (pinfunction "VDDA_1P8_LVDS_U23") (pintype "passive"))
      (node (ref "U1") (pin "W17") (pinfunction "VDDA_1P8_SPLL_W17") (pintype "passive"))
      (node (ref "U1") (pin "W23") (pinfunction "VDDA_1P8_XTAL_27M_W23") (pintype "passive"))
      (node (ref "U1") (pin "W24") (pinfunction "VDDA_1P8_XTAL_25M_W24") (pintype "passive"))
    )
    (net (code "11") (name "VDD_1V8") (class "Default")
      (node (ref "C100") (pin "1") (pinfunction "1_1") (pintype "passive"))
      (node (ref "C95") (pin "1") (pinfunction "1_1") (pintype "passive"))
      (node (ref "C96") (pin "2") (pinfunction "2_2") (pintype "passive"))
      (node (ref "C97") (pin "2") (pinfunction "2_2") (pintype "passive"))
      (node (ref "C98") (pin "2") (pinfunction "2_2") (pintype "passive"))
      (node (ref "C99") (pin "2") (pinfunction "2_2") (pintype "passive"))
      (node (ref "U2") (pin "F1") (pinfunction "VDD1_F1_F1") (pintype "power_in"))
      (node (ref "U2") (pin "F12") (pinfunction "VDD1_F12_F12") (pintype "power_in"))
      (node (ref "U2") (pin "G4") (pinfunction "VDD1_G4_G4") (pintype "power_in"))
      (node (ref "U2") (pin "G9") (pinfunction "VDD1_G9_G9") (pintype "power_in"))
      (node (ref "U2") (pin "T4") (pinfunction "VDD1_T4_T4") (pintype "power_in"))
      (node (ref "U2") (pin "T9") (pinfunction "VDD1_T9_T9") (pintype "power_in"))
      (node (ref "U2") (pin "U1") (pinfunction "VDD1_U1_U1") (pintype "power_in"))
      (node (ref "U2") (pin "U12") (pinfunction "VDD1_U12_U12") (pintype "power_in"))
    )
    (net (code "12") (name "VDD_ARM_0V9") (class "Default")
      (node (ref "C38") (pin "1") (pinfunction "1_1") (pintype "passive"))
      (node (ref "C39") (pin "1") (pinfunction "1_1") (pintype "passive"))
      (node (ref "C40") (pin "1") (pinfunction "1_1") (pintype "passive"))
      (node (ref "C41") (pin "1") (pinfunction "1_1") (pintype "passive"))
      (node (ref "C42") (pin "1") (pinfunction "1_1") (pintype "passive"))
      (node (ref "C43") (pin "1") (pinfunction "1_1") (pintype "passive"))
      (node (ref "C53") (pin "1") (pinfunction "1_1") (pintype "passive"))
      (node (ref "C54") (pin "1") (pinfunction "1_1") (pintype "passive"))
      (node (ref "C55") (pin "1") (pinfunction "1_1") (pintype "passive"))
      (node (ref "C56") (pin "1") (pinfunction "1_1") (pintype "passive"))
      (node (ref "C57") (pin "1") (pinfunction "1_1") (pintype "passive"))
      (node (ref "C58") (pin "1") (pinfunction "1_1") (pintype "passive"))
      (node (ref "U1") (pin "G14") (pinfunction "VDD_ARM13_G14") (pintype "passive"))
      (node (ref "U1") (pin "G15") (pinfunction "VDD_ARM1_G15") (pintype "passive"))
      (node (ref "U1") (pin "G16") (pinfunction "VDD_ARM7_G16") (pintype "passive"))
      (node (ref "U1") (pin "H14") (pinfunction "VDD_ARM14_H14") (pintype "passive"))
      (node (ref "U1") (pin "H15") (pinfunction "VDD_ARM2_H15") (pintype "passive"))
      (node (ref "U1") (pin "H16") (pinfunction "VDD_ARM8_H16") (pintype "passive"))
      (node (ref "U1") (pin "J15") (pinfunction "VDD_ARM3_J15") (pintype "passive"))
      (node (ref "U1") (pin "J16") (pinfunction "VDD_ARM9_J16") (pintype "passive"))
      (node (ref "U1") (pin "K15") (pinfunction "VDD_ARM4_K15") (pintype "passive"))
      (node (ref "U1") (pin "K16") (pinfunction "VDD_ARM10_K16") (pintype "passive"))
      (node (ref "U1") (pin "L15") (pinfunction "VDD_ARM5_L15") (pintype "passive"))
      (node (ref "U1") (pin "L16") (pinfunction "VDD_ARM11_L16") (pintype "passive"))
      (node (ref "U1") (pin "M15") (pinfunction "VDD_ARM6_M15") (pintype "passive"))
      (node (ref "U1") (pin "M16") (pinfunction "VDD_ARM12_M16") (pintype "passive"))
    )
    (net (code "13") (name "VDD_DRAM_0V9") (class "Default")
      (node (ref "C103") (pin "1") (pinfunction "1_1") (pintype "passive"))
      (node (ref "C104") (pin "1") (pinfunction "1_1") (pintype "passive"))
      (node (ref "C105") (pin "1") (pinfunction "1_1") (pintype "passive"))
      (node (ref "C106") (pin "1") (pinfunction "1_1") (pintype "passive"))
      (node (ref "C107") (pin "1") (pinfunction "1_1") (pintype "passive"))
      (node (ref "C108") (pin "1") (pinfunction "1_1") (pintype "passive"))
      (node (ref "C109") (pin "1") (pinfunction "1_1") (pintype "passive"))
      (node (ref "C114") (pin "1") (pinfunction "1_1") (pintype "passive"))
      (node (ref "C115") (pin "1") (pinfunction "1_1") (pintype "passive"))
      (node (ref "C116") (pin "1") (pinfunction "1_1") (pintype "passive"))
      (node (ref "C117") (pin "1") (pinfunction "1_1") (pintype "passive"))
      (node (ref "C118") (pin "1") (pinfunction "1_1") (pintype "passive"))
      (node (ref "C119") (pin "1") (pinfunction "1_1") (pintype "passive"))
      (node (ref "C120") (pin "1") (pinfunction "1_1") (pintype "passive"))
      (node (ref "C89") (pin "1") (pinfunction "1_1") (pintype "passive"))
      (node (ref "C90") (pin "1") (pinfunction "1_1") (pintype "passive"))
      (node (ref "C91") (pin "1") (pinfunction "1_1") (pintype "passive"))
      (node (ref "C92") (pin "1") (pinfunction "1_1") (pintype "passive"))
      (node (ref "C93") (pin "1") (pinfunction "1_1") (pintype "passive"))
      (node (ref "C94") (pin "1") (pinfunction "1_1") (pintype "passive"))
      (node (ref "U1") (pin "U10") (pinfunction "VDD_DRAM11_U10") (pintype "passive"))
      (node (ref "U1") (pin "U11") (pinfunction "VDD_DRAM8_U11") (pintype "passive"))
      (node (ref "U1") (pin "U12") (pinfunction "VDD_DRAM10_U12") (pintype "passive"))
      (node (ref "U1") (pin "U13") (pinfunction "VDD_DRAM12_U13") (pintype "passive"))
      (node (ref "U1") (pin "U14") (pinfunction "VDD_DRAM9_U14") (pintype "passive"))
      (node (ref "U1") (pin "V10") (pinfunction "VDD_DRAM7_V10") (pintype "passive"))
      (node (ref "U1") (pin "V11") (pinfunction "VDD_DRAM6_V11") (pintype "passive"))
      (node (ref "U1") (pin "V12") (pinfunction "VDD_DRAM5_V12") (pintype "passive"))
      (node (ref "U1") (pin "V13") (pinfunction "VDD_DRAM4_V13") (pintype "passive"))
      (node (ref "U1") (pin "V14") (pinfunction "VDD_DRAM3_V14") (pintype "passive"))
      (node (ref "U1") (pin "V15") (pinfunction "VDD_DRAM2_V15") (pintype "passive"))
      (node (ref "U1") (pin "V9") (pinfunction "VDD_DRAM1_V9") (pintype "passive"))
      (node (ref "U1") (pin "Y10") (pinfunction "VDD_DRAM18_Y10") (pintype "passive"))
      (node (ref "U1") (pin "Y16") (pinfunction "VDD_DRAM17_Y16") (pintype "passive"))
      (node (ref "U1") (pin "Y18") (pinfunction "VDD_DRAM16_Y18") (pintype "passive"))
      (node (ref "U1") (pin "Y20") (pinfunction "VDD_DRAM15_Y20") (pintype "passive"))
      (node (ref "U1") (pin "Y6") (pinfunction "VDD_DRAM13_Y6") (pintype "passive"))
      (node (ref "U1") (pin "Y8") (pinfunction "VDD_DRAM14_Y8") (pintype "passive"))
    )
    (net (code "14") (name "VDD_GPU_0V9") (class "Default")
      (node (ref "C76") (pin "1") (pinfunction "1_1") (pintype "passive"))
      (node (ref "C77") (pin "1") (pinfunction "1_1") (pintype "passive"))
      (node (ref "C78") (pin "1") (pinfunction "1_1") (pintype "passive"))
      (node (ref "C79") (pin "1") (pinfunction "1_1") (pintype "passive"))
      (node (ref "C80") (pin "1") (pinfunction "1_1") (pintype "passive"))
      (node (ref "C81") (pin "1") (pinfunction "1_1") (pintype "passive"))
      (node (ref "C82") (pin "1") (pinfunction "1_1") (pintype "passive"))
      (node (ref "C83") (pin "1") (pinfunction "1_1") (pintype "passive"))
      (node (ref "C84") (pin "1") (pinfunction "1_1") (pintype "passive"))
      (node (ref "C85") (pin "1") (pinfunction "1_1") (pintype "passive"))
      (node (ref "U1") (pin "J10") (pinfunction "VDD_GPU5_J10") (pintype "passive"))
      (node (ref "U1") (pin "J9") (pinfunction "VDD_GPU1_J9") (pintype "passive"))
      (node (ref "U1") (pin "K10") (pinfunction "VDD_GPU6_K10") (pintype "passive"))
      (node (ref "U1") (pin "K9") (pinfunction "VDD_GPU2_K9") (pintype "passive"))
      (node (ref "U1") (pin "L10") (pinfunction "VDD_GPU7_L10") (pintype "passive"))
      (node (ref "U1") (pin "L9") (pinfunction "VDD_GPU3_L9") (pintype "passive"))
      (node (ref "U1") (pin "M10") (pinfunction "VDD_GPU8_M10") (pintype "passive"))
      (node (ref "U1") (pin "M9") (pinfunction "VDD_GPU4_M9") (pintype "passive"))
    )
    (net (code "15") (name "VDD_PHY_0V9") (class "Default")
      (node (ref "C110") (pin "1") (pinfunction "1_1") (pintype "passive"))
      (node (ref "C111") (pin "1") (pinfunction "1_1") (pintype "passive"))
      (node (ref "C112") (pin "1") (pinfunction "1_1") (pintype "passive"))
      (node (ref "C113") (pin "2") (pinfunction "2_2") (pintype "passive"))
      (node (ref "C44") (pin "1") (pinfunction "1_1") (pintype "passive"))
      (node (ref "C45") (pin "1") (pinfunction "1_1") (pintype "passive"))
      (node (ref "C46") (pin "2") (pinfunction "2_2") (pintype "passive"))
      (node (ref "C71") (pin "1") (pinfunction "1_1") (pintype "passive"))
      (node (ref "C72") (pin "1") (pinfunction "1_1") (pintype "passive"))
      (node (ref "C73") (pin "2") (pinfunction "2_2") (pintype "passive"))
      (node (ref "C86") (pin "1") (pinfunction "1_1") (pintype "passive"))
      (node (ref "C87") (pin "1") (pinfunction "1_1") (pintype "passive"))
      (node (ref "C88") (pin "2") (pinfunction "2_2") (pintype "passive"))
      (node (ref "FB2") (pin "2") (pinfunction "2_2") (pintype "passive"))
      (node (ref "U1") (pin "C11") (pinfunction "USB2_VPTX_C11") (pintype "passive"))
      (node (ref "U1") (pin "C12") (pinfunction "USB1_VPTX_C12") (pintype "passive"))
      (node (ref "U1") (pin "D11") (pinfunction "USB2_VP_D11") (pintype "passive"))
      (node (ref "U1") (pin "D12") (pinfunction "USB1_VP_D12") (pintype "passive"))
      (node (ref "U1") (pin "E11") (pinfunction "USB2_DVDD_E11") (pintype "passive"))
      (node (ref "U1") (pin "E12") (pinfunction "USB1_DVDD_E12") (pintype "passive"))
      (node (ref "U1") (pin "E17") (pinfunction "MIPI_VDDA1_E17") (pintype "passive"))
      (node (ref "U1") (pin "E18") (pinfunction "MIPI_VDDA2_E18") (pintype "passive"))
      (node (ref "U1") (pin "F17") (pinfunction "MIPI_VDDA3_F17") (pintype "passive"))
      (node (ref "U1") (pin "F18") (pinfunction "MIPI_VDDA4_F18") (pintype "passive"))
      (node (ref "U1") (pin "F19") (pinfunction "MIPI_VDDPLL_F19") (pintype "passive"))
      (node (ref "U1") (pin "F22") (pinfunction "PCIE_VP2_F22") (pintype "passive"))
      (node (ref "U1") (pin "F23") (pinfunction "PCIE_VPTX2_F23") (pintype "passive"))
      (node (ref "U1") (pin "G22") (pinfunction "PCIE_VP1_G22") (pintype "passive"))
      (node (ref "U1") (pin "G23") (pinfunction "PCIE_VPTX1_G23") (pintype "passive"))
      (node (ref "U1") (pin "U3") (pinfunction "HDMI_AVDDCORE2_U3") (pintype "passive"))
      (node (ref "U1") (pin "U4") (pinfunction "HDMI_AVDDCORE1_U4") (pintype "passive"))
      (node (ref "U1") (pin "V3") (pinfunction "HDMI_AVDDCLK_V3") (pintype "passive"))
    )
    (net (code "16") (name "VDD_PHY_1V8") (class "Default")
      (node (ref "C101") (pin "1") (pinfunction "1_1") (pintype "passive"))
      (node (ref "C102") (pin "2") (pinfunction "2_2") (pintype "passive"))
      (node (ref "C59") (pin "1") (pinfunction "1_1") (pintype "passive"))
      (node (ref "C60") (pin "2") (pinfunction "2_2") (pintype "passive"))
      (node (ref "C74") (pin "1") (pinfunction "1_1") (pintype "passive"))
      (node (ref "C75") (pin "2") (pinfunction "2_2") (pintype "passive"))
      (node (ref "U1") (pin "C18") (pinfunction "MIPI_VDDHA1_C18") (pintype "passive"))
      (node (ref "U1") (pin "D17") (pinfunction "MIPI_VDDHA2_D17") (pintype "passive"))
      (node (ref "U1") (pin "D18") (pinfunction "MIPI_VDDHA3_D18") (pintype "passive"))
      (node (ref "U1") (pin "H23") (pinfunction "PCIE_VPH1_H23") (pintype "passive"))
      (node (ref "U1") (pin "J23") (pinfunction "PCIE_VPH2_J23") (pintype "passive"))
      (node (ref "U1") (pin "P2") (pinfunction "HDMI_AVDDIO_P2") (pintype "passive"))
    )
    (net (code "17") (name "VDD_PHY_3V3") (class "Default")
      (node (ref "C34") (pin "1") (pinfunction "1_1") (pintype "passive"))
      (node (ref "C35") (pin "1") (pinfunction "1_1") (pintype "passive"))
      (node (ref "C36") (pin "2") (pinfunction "2_2") (pintype "passive"))
      (node (ref "U1") (pin "F11") (pinfunction "USB2_VPH_F11") (pintype "passive"))
      (node (ref "U1") (pin "F12") (pinfunction "USB1_VPH_F12") (pintype "passive"))
      (node (ref "U1") (pin "G11") (pinfunction "USB2_VDD33_G11") (pintype "passive"))
      (node (ref "U1") (pin "G12") (pinfunction "USB1_VDD33_G12") (pintype "passive"))
    )
    (net (code "18") (name "VDD_SNVS_0V9") (class "Default")
      (node (ref "C5") (pin "1") (pinfunction "1_1") (pintype "passive"))
      (node (ref "U1") (pin "R18") (pinfunction "VDD_SNVS_R18") (pintype "passive"))
    )
    (net (code "19") (name "VDD_SOC_0V9") (class "Default")
      (node (ref "C12") (pin "1") (pinfunction "1_1") (pintype "passive"))
      (node (ref "C13") (pin "1") (pinfunction "1_1") (pintype "passive"))
      (node (ref "C14") (pin "1") (pinfunction "1_1") (pintype "passive"))
      (node (ref "C15") (pin "1") (pinfunction "1_1") (pintype "passive"))
      (node (ref "C16") (pin "1") (pinfunction "1_1") (pintype "passive"))
      (node (ref "C17") (pin "1") (pinfunction "1_1") (pintype "passive"))
      (node (ref "C18") (pin "1") (pinfunction "1_1") (pintype "passive"))
      (node (ref "C19") (pin "1") (pinfunction "1_1") (pintype "passive"))
      (node (ref "C20") (pin "1") (pinfunction "1_1") (pintype "passive"))
      (node (ref "C21") (pin "1") (pinfunction "1_1") (pintype "passive"))
      (node (ref "C22") (pin "1") (pinfunction "1_1") (pintype "passive"))
      (node (ref "C23") (pin "1") (pinfunction "1_1") (pintype "passive"))
      (node (ref "C24") (pin "1") (pinfunction "1_1") (pintype "passive"))
      (node (ref "FB1") (pin "2") (pinfunction "2_2") (pintype "passive"))
      (node (ref "U1") (pin "K12") (pinfunction "VDD_SOC11_K12") (pintype "passive"))
      (node (ref "U1") (pin "L12") (pinfunction "VDD_SOC12_L12") (pintype "passive"))
      (node (ref "U1") (pin "L13") (pinfunction "VDD_SOC17_L13") (pintype "passive"))
      (node (ref "U1") (pin "M12") (pinfunction "VDD_SOC13_M12") (pintype "passive"))
      (node (ref "U1") (pin "M13") (pinfunction "VDD_SOC18_M13") (pintype "passive"))
      (node (ref "U1") (pin "N13") (pinfunction "VDD_SOC19_N13") (pintype "passive"))
      (node (ref "U1") (pin "P12") (pinfunction "VDD_SOC15_P12") (pintype "passive"))
      (node (ref "U1") (pin "P13") (pinfunction "VDD_SOC20_P13") (pintype "passive"))
      (node (ref "U1") (pin "P15") (pinfunction "VDD_SOC16_P15") (pintype "passive"))
      (node (ref "U1") (pin "P16") (pinfunction "VDD_SOC14_P16") (pintype "passive"))
      (node (ref "U1") (pin "R10") (pinfunction "VDD_SOC3_R10") (pintype "passive"))
      (node (ref "U1") (pin "R11") (pinfunction "VDD_SOC4_R11") (pintype "passive"))
      (node (ref "U1") (pin "R12") (pinfunction "VDD_SOC5_R12") (pintype "passive"))
      (node (ref "U1") (pin "R13") (pinfunction "VDD_SOC6_R13") (pintype "passive"))
      (node (ref "U1") (pin "R14") (pinfunction "VDD_SOC7_R14") (pintype "passive"))
      (node (ref "U1") (pin "R15") (pinfunction "VDD_SOC8_R15") (pintype "passive"))
      (node (ref "U1") (pin "R16") (pinfunction "VDD_SOC9_R16") (pintype "passive"))
      (node (ref "U1") (pin "R8") (pinfunction "VDD_SOC1_R8") (pintype "passive"))
      (node (ref "U1") (pin "R9") (pinfunction "VDD_SOC2_R9") (pintype "passive"))
      (node (ref "U1") (pin "T17") (pinfunction "VDD_SOC21_T17") (pintype "passive"))
      (node (ref "U1") (pin "T8") (pinfunction "VDD_SOC10_T8") (pintype "passive"))
    )
    (net (code "20") (name "VDD_VPU_0V9") (class "Default")
      (node (ref "C61") (pin "1") (pinfunction "1_1") (pintype "passive"))
      (node (ref "C62") (pin "1") (pinfunction "1_1") (pintype "passive"))
      (node (ref "C63") (pin "1") (pinfunction "1_1") (pintype "passive"))
      (node (ref "C64") (pin "1") (pinfunction "1_1") (pintype "passive"))
      (node (ref "C65") (pin "1") (pinfunction "1_1") (pintype "passive"))
      (node (ref "C66") (pin "1") (pinfunction "1_1") (pintype "passive"))
      (node (ref "C67") (pin "1") (pinfunction "1_1") (pintype "passive"))
      (node (ref "C68") (pin "1") (pinfunction "1_1") (pintype "passive"))
      (node (ref "C69") (pin "1") (pinfunction "1_1") (pintype "passive"))
      (node (ref "C70") (pin "1") (pinfunction "1_1") (pintype "passive"))
      (node (ref "U1") (pin "N10") (pinfunction "VDD_VPU3_N10") (pintype "passive"))
      (node (ref "U1") (pin "N8") (pinfunction "VDD_VPU1_N8") (pintype "passive"))
      (node (ref "U1") (pin "N9") (pinfunction "VDD_VPU2_N9") (pintype "passive"))
      (node (ref "U1") (pin "P10") (pinfunction "VDD_VPU5_P10") (pintype "passive"))
      (node (ref "U1") (pin "P9") (pinfunction "VDD_VPU4_P9") (pintype "passive"))
    )
  )
)
